# citizen_science_flora_RP2040.net
KiCad netlist of a schematic drawn in EAGLE
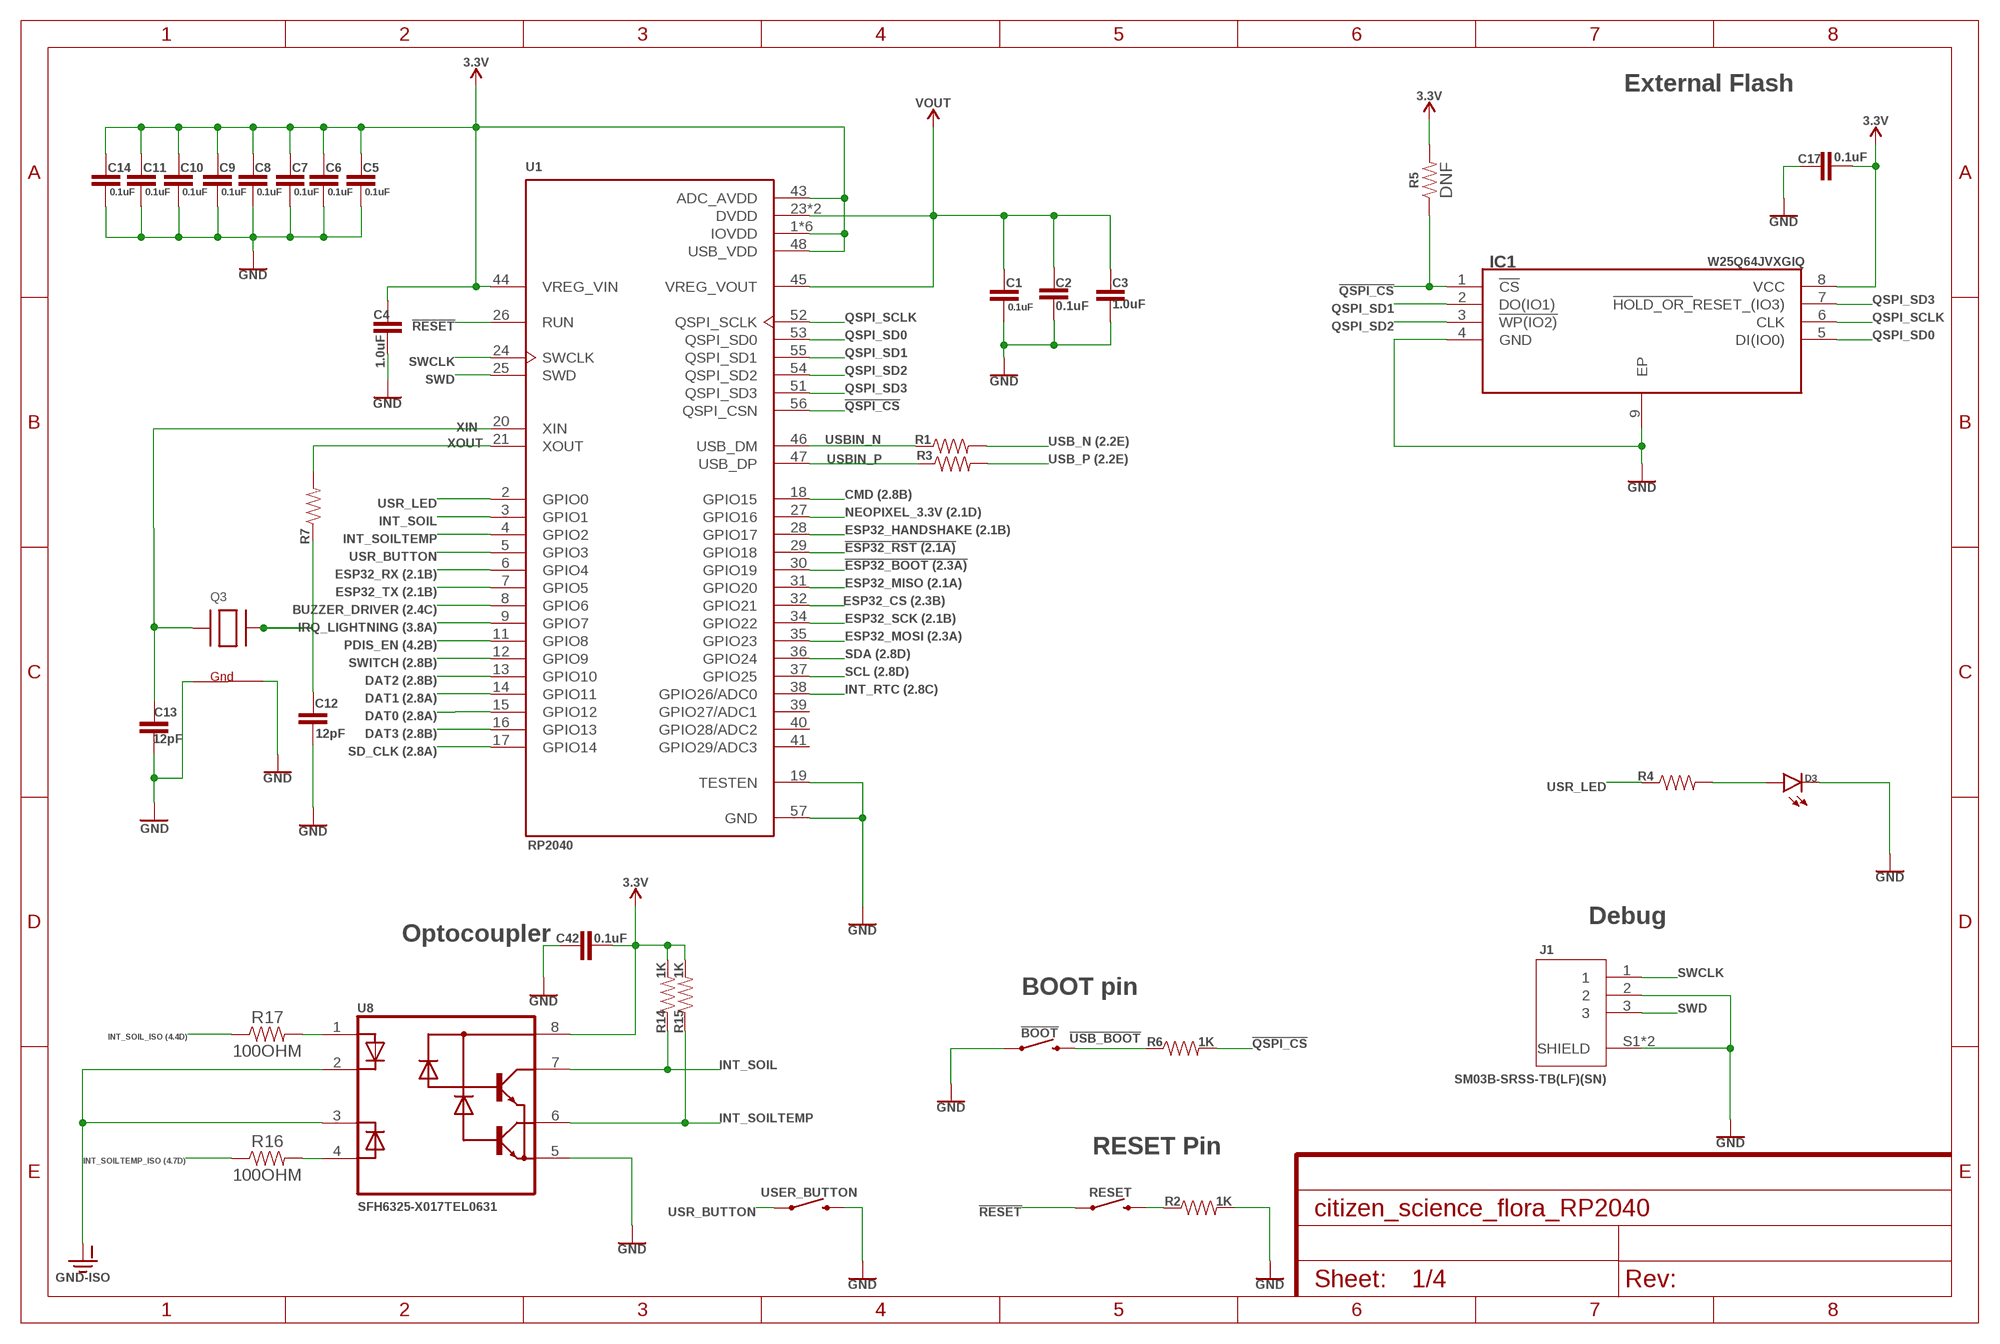
[diagram p0: schematic, sheet 1]
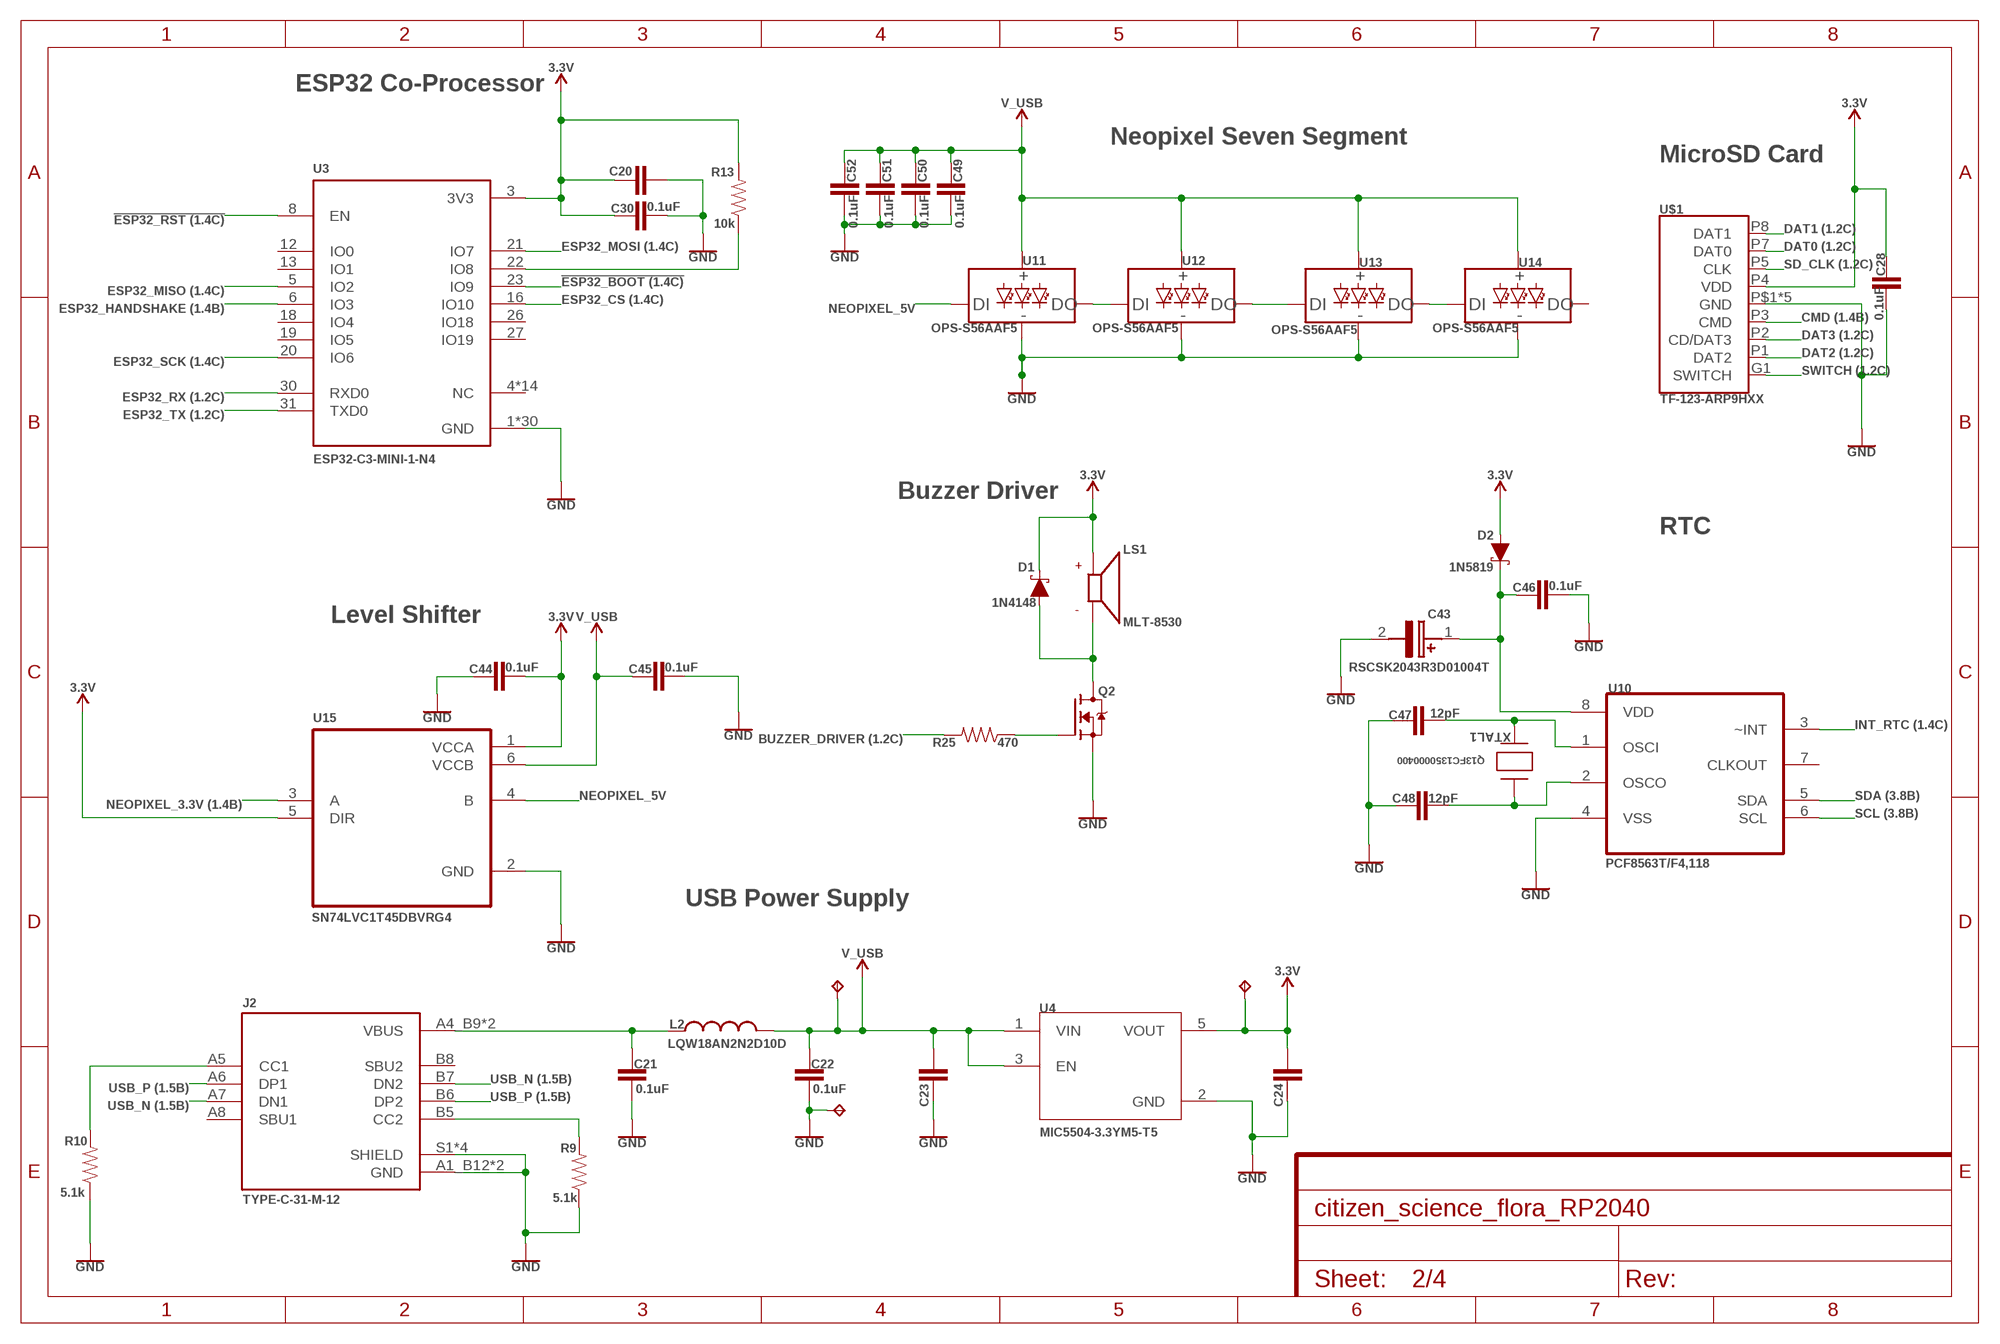
[diagram p1: schematic, sheet 2]
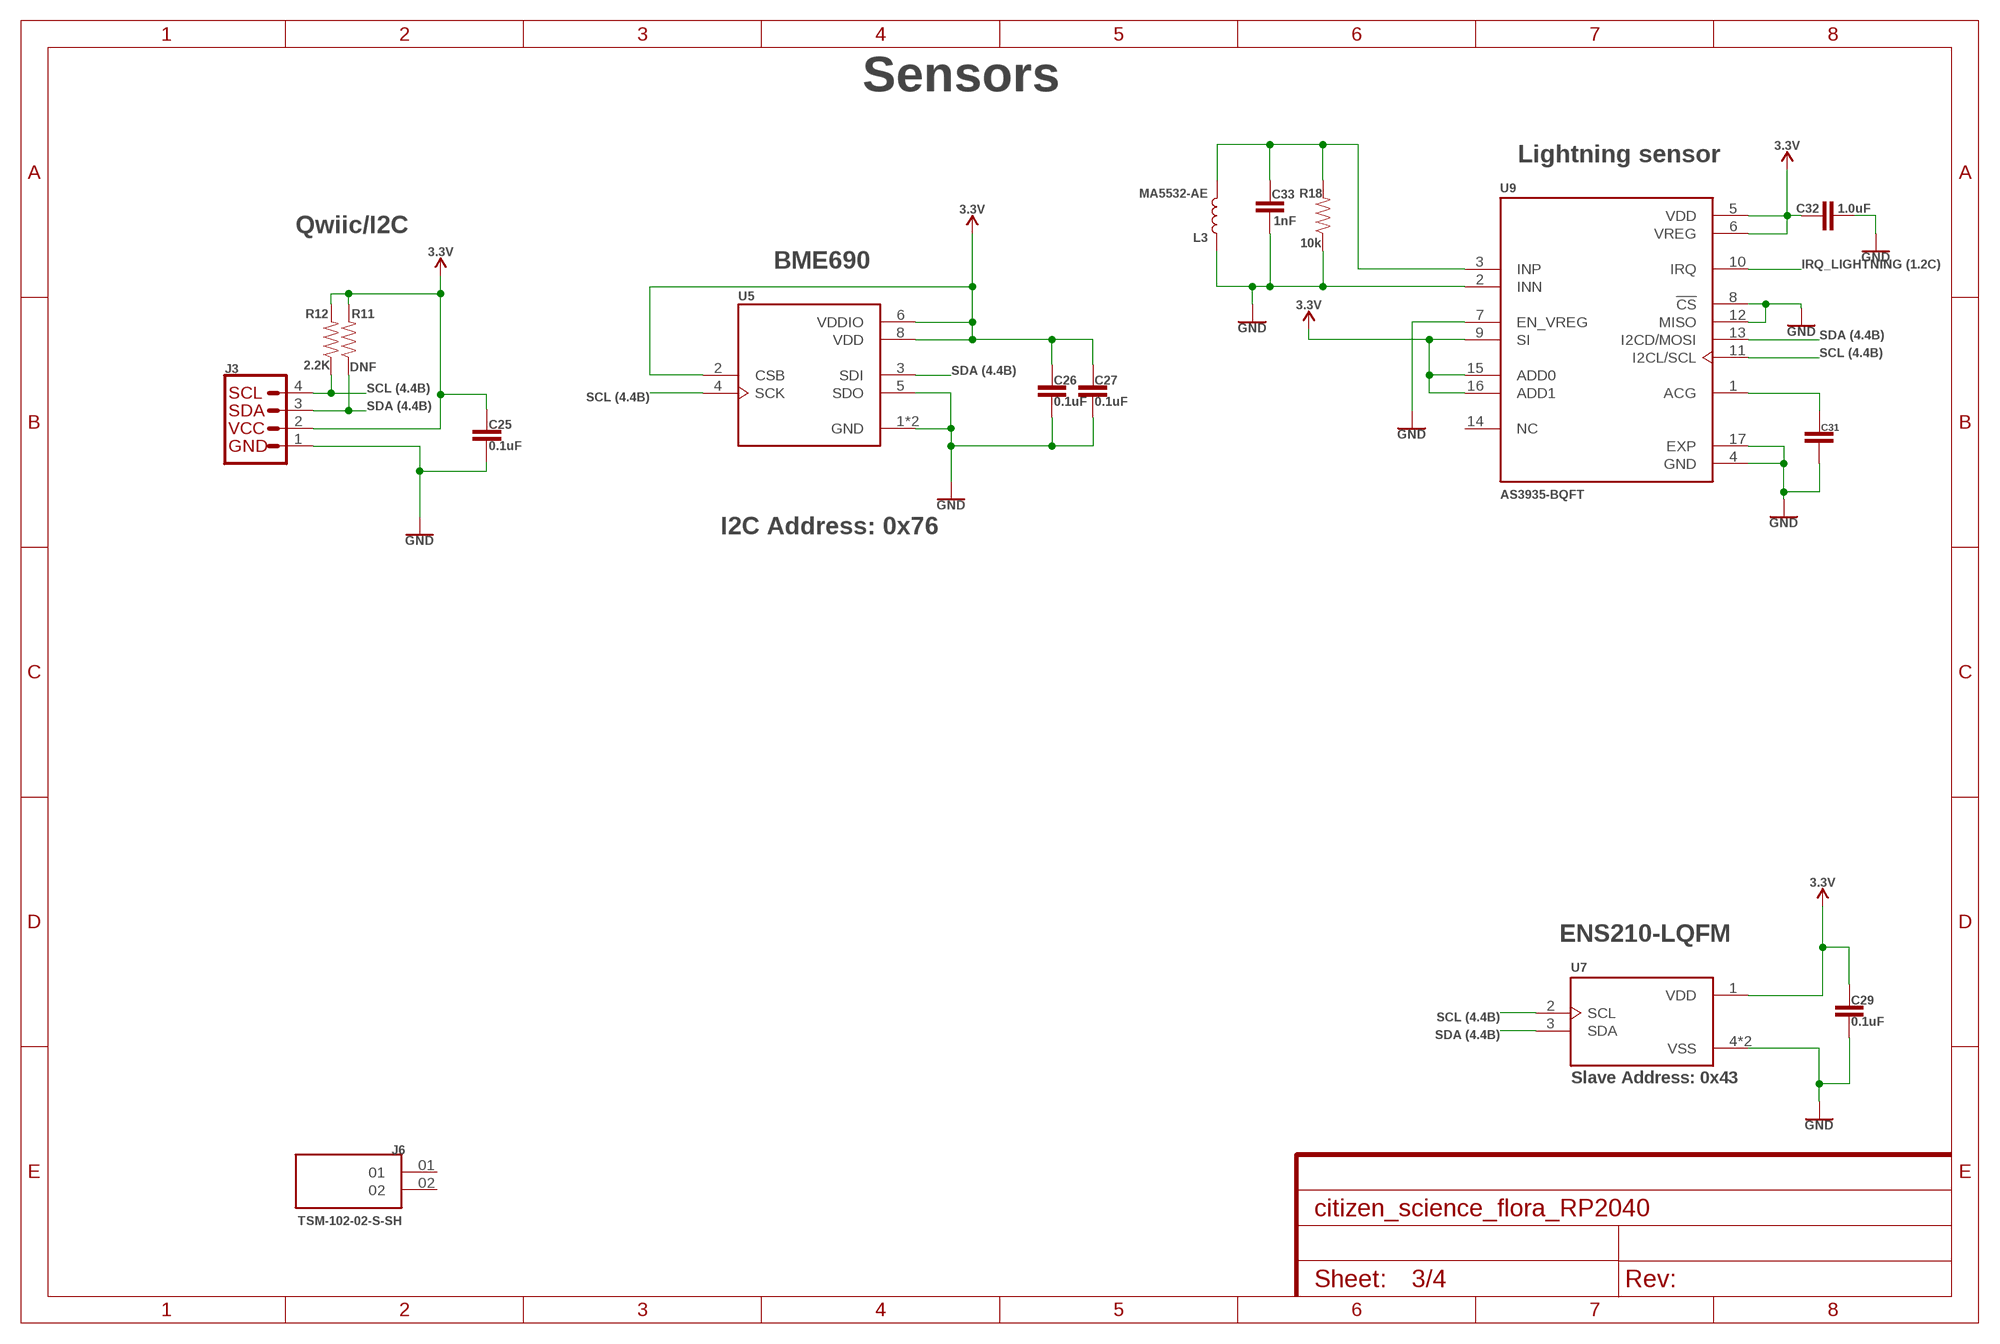
[diagram p2: schematic, sheet 3]
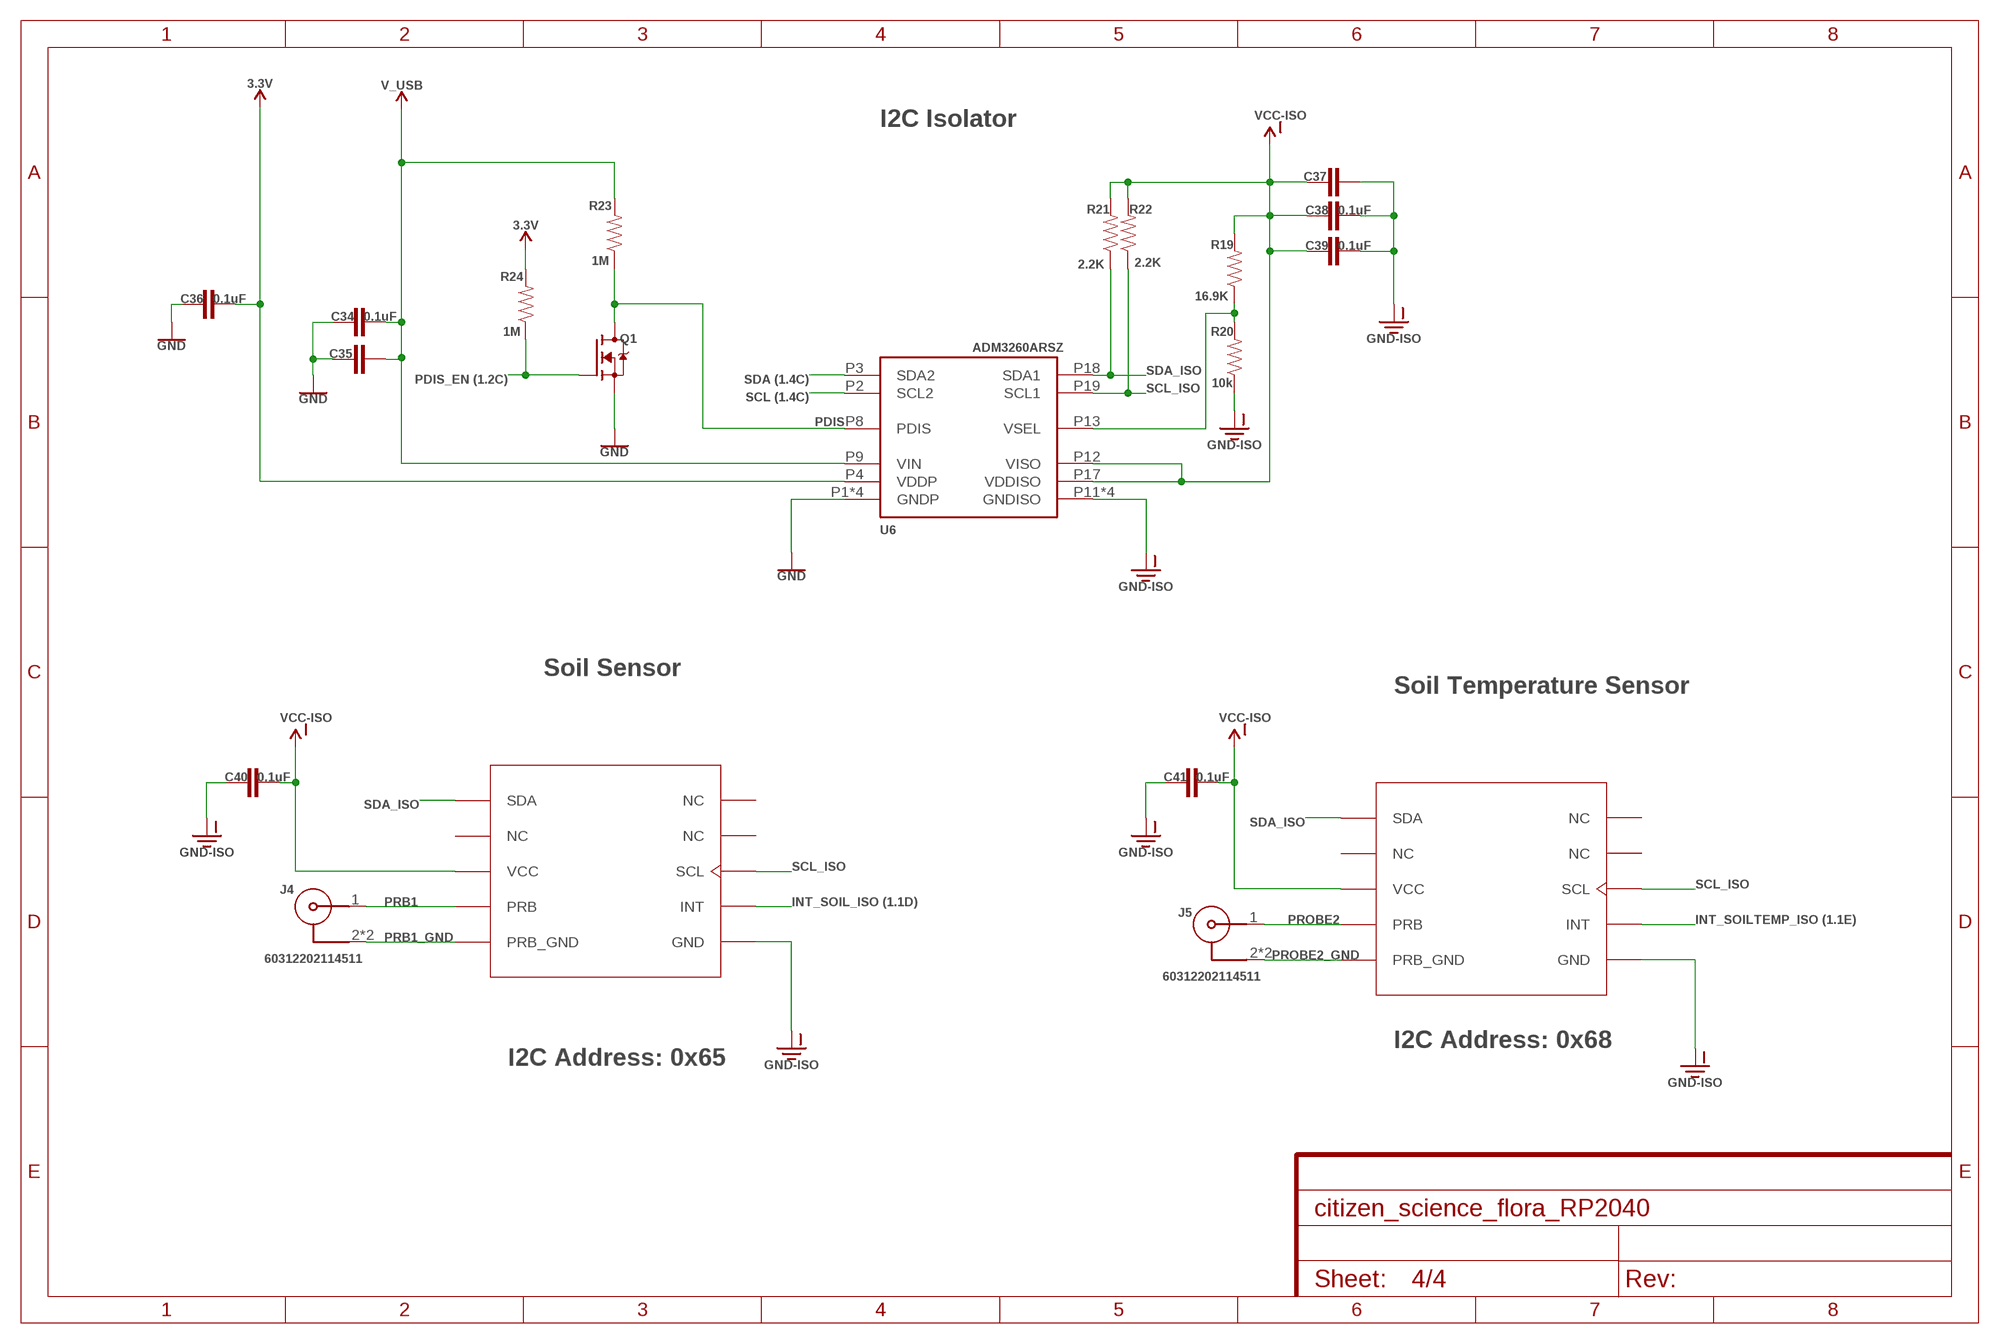
[diagram p3: schematic, sheet 4]

(export (version "E")
  (design (tool "Eeschema 10.0.6"))
  (components
    (comp (ref "C34")
      (value "0.1uF")
      (footprint "eagle-import:0402")
      (libsource (lib "eagle-import") (part "0.1UF-0402-6.3V-10%-X7R"))
    )
    (comp (ref "C35")
      (value "10UF0402")
      (footprint "eagle-import:0402")
      (libsource (lib "eagle-import") (part "10UF0402"))
    )
    (comp (ref "C36")
      (value "0.1uF")
      (footprint "eagle-import:0402")
      (libsource (lib "eagle-import") (part "0.1UF-0402-6.3V-10%-X7R"))
    )
    (comp (ref "C37")
      (value "10UF0402")
      (footprint "eagle-import:0402")
      (libsource (lib "eagle-import") (part "10UF0402"))
    )
    (comp (ref "C38")
      (value "0.1uF")
      (footprint "eagle-import:0402")
      (libsource (lib "eagle-import") (part "0.1UF-0402-6.3V-10%-X7R"))
    )
    (comp (ref "C39")
      (value "0.1uF")
      (footprint "eagle-import:0402")
      (libsource (lib "eagle-import") (part "0.1UF-0402-6.3V-10%-X7R"))
    )
    (comp (ref "C40")
      (value "0.1uF")
      (footprint "eagle-import:0402")
      (libsource (lib "eagle-import") (part "0.1UF-0402-6.3V-10%-X7R"))
    )
    (comp (ref "C41")
      (value "0.1uF")
      (footprint "eagle-import:0402")
      (libsource (lib "eagle-import") (part "0.1UF-0402-6.3V-10%-X7R"))
    )
    (comp (ref "J4")
      (value "60312202114511")
      (footprint "eagle-import:60312202114511")
      (fields (field (name "MF") "Wurth Electronics"))
      (libsource (lib "eagle-import") (part "60312202114511"))
    )
    (comp (ref "J5")
      (value "60312202114511")
      (footprint "eagle-import:60312202114511")
      (fields (field (name "MF") "Wurth Electronics"))
      (libsource (lib "eagle-import") (part "60312202114511"))
    )
    (comp (ref "Q1")
      (value "BSS138")
      (footprint "eagle-import:SOT95P240X111-3N")
      (fields (field (name "MF") "onsemi"))
      (libsource (lib "eagle-import") (part "BSS138"))
    )
    (comp (ref "R19")
      (value "16.9K")
      (footprint "eagle-import:0402")
      (libsource (lib "eagle-import") (part "RESISTOR0402"))
    )
    (comp (ref "R20")
      (value "10k")
      (footprint "eagle-import:0402")
      (libsource (lib "eagle-import") (part "SparkFun-Resistors_Sai_10KOHM-0402-1/16W-1%"))
    )
    (comp (ref "R21")
      (value "2.2K")
      (footprint "eagle-import:0402")
      (libsource (lib "eagle-import") (part "2.2KOHM-0402-1/16W-1%"))
    )
    (comp (ref "R22")
      (value "2.2K")
      (footprint "eagle-import:0402")
      (libsource (lib "eagle-import") (part "2.2KOHM-0402-1/16W-1%"))
    )
    (comp (ref "R23")
      (value "1M")
      (footprint "eagle-import:0402")
      (libsource (lib "eagle-import") (part "1MOHM-0402-1/16W-5%"))
    )
    (comp (ref "R24")
      (value "1M")
      (footprint "eagle-import:0402")
      (libsource (lib "eagle-import") (part "1MOHM-0402-1/16W-5%"))
    )
    (comp (ref "U$2")
      (value "PH-OEM")
      (footprint "eagle-import:PH_SENSOR")
      (libsource (lib "eagle-import") (part "PH-OEM"))
    )
    (comp (ref "U$3")
      (value "PH-OEM")
      (footprint "eagle-import:PH_SENSOR")
      (libsource (lib "eagle-import") (part "PH-OEM"))
    )
    (comp (ref "U6")
      (value "ADM3260ARSZ")
      (footprint "eagle-import:SSOP20")
      (fields (field (name "MF") "Analog Devices"))
      (libsource (lib "eagle-import") (part "ADM3260ARSZ"))
    )
    (comp (ref "!BOOT")
      (value "MOMENTARY-SWITCH-SPST-SMD-4.6X2.8MM")
      (footprint "eagle-import:TACTILE_SWITCH_SMD_4.6X2.8MM")
      (libsource (lib "eagle-import") (part "MOMENTARY-SWITCH-SPST-SMD-4.6X2.8MM"))
    )
    (comp (ref "C1")
      (value "0.1uF")
      (footprint "eagle-import:0402")
      (libsource (lib "eagle-import") (part "SparkFun-Capacitors_Sai_0.1UF-0402-6.3V-10%-X7R"))
    )
    (comp (ref "C2")
      (value "0.1uF")
      (footprint "eagle-import:0402")
      (libsource (lib "eagle-import") (part "SparkFun-Capacitors_Sai_0.1UF-0402-6.3V-10%-X7R"))
    )
    (comp (ref "C3")
      (value "1.0uF")
      (footprint "eagle-import:0402")
      (libsource (lib "eagle-import") (part "SparkFun-Capacitors_Sai_1.0UF-0402-16V-10%"))
    )
    (comp (ref "C4")
      (value "1.0uF")
      (footprint "eagle-import:0402")
      (libsource (lib "eagle-import") (part "SparkFun-Capacitors_Sai_1.0UF-0402-16V-10%"))
    )
    (comp (ref "C5")
      (value "0.1uF")
      (footprint "eagle-import:0402")
      (libsource (lib "eagle-import") (part "SparkFun-Capacitors_Sai_0.1UF-0402-6.3V-10%-X7R"))
    )
    (comp (ref "C6")
      (value "0.1uF")
      (footprint "eagle-import:0402")
      (libsource (lib "eagle-import") (part "SparkFun-Capacitors_Sai_0.1UF-0402-6.3V-10%-X7R"))
    )
    (comp (ref "C7")
      (value "0.1uF")
      (footprint "eagle-import:0402")
      (libsource (lib "eagle-import") (part "SparkFun-Capacitors_Sai_0.1UF-0402-6.3V-10%-X7R"))
    )
    (comp (ref "C8")
      (value "0.1uF")
      (footprint "eagle-import:0402")
      (libsource (lib "eagle-import") (part "SparkFun-Capacitors_Sai_0.1UF-0402-6.3V-10%-X7R"))
    )
    (comp (ref "C9")
      (value "0.1uF")
      (footprint "eagle-import:0402")
      (libsource (lib "eagle-import") (part "SparkFun-Capacitors_Sai_0.1UF-0402-6.3V-10%-X7R"))
    )
    (comp (ref "C10")
      (value "0.1uF")
      (footprint "eagle-import:0402")
      (libsource (lib "eagle-import") (part "SparkFun-Capacitors_Sai_0.1UF-0402-6.3V-10%-X7R"))
    )
    (comp (ref "C11")
      (value "0.1uF")
      (footprint "eagle-import:0402")
      (libsource (lib "eagle-import") (part "SparkFun-Capacitors_Sai_0.1UF-0402-6.3V-10%-X7R"))
    )
    (comp (ref "C12")
      (value "12pF")
      (footprint "eagle-import:0402")
      (libsource (lib "eagle-import") (part "SparkFun-Capacitors_Sai_12PF-0402-50V-5%"))
    )
    (comp (ref "C13")
      (value "12pF")
      (footprint "eagle-import:0402")
      (libsource (lib "eagle-import") (part "SparkFun-Capacitors_Sai_12PF-0402-50V-5%"))
    )
    (comp (ref "C14")
      (value "0.1uF")
      (footprint "eagle-import:0402")
      (libsource (lib "eagle-import") (part "SparkFun-Capacitors_Sai_0.1UF-0402-6.3V-10%-X7R"))
    )
    (comp (ref "C17")
      (value "0.1uF")
      (footprint "eagle-import:0402")
      (libsource (lib "eagle-import") (part "0.1UF-0402-6.3V-10%-X7R"))
    )
    (comp (ref "C42")
      (value "0.1uF")
      (footprint "eagle-import:0402")
      (libsource (lib "eagle-import") (part "0.1UF-0402-6.3V-10%-X7R"))
    )
    (comp (ref "D3")
      (value "LED0603")
      (footprint "eagle-import:LED-0603")
      (libsource (lib "eagle-import") (part "LED0603"))
    )
    (comp (ref "IC1")
      (value "W25Q64JVXGIQ")
      (footprint "eagle-import:SON80P400X400X50-9N")
      (libsource (lib "eagle-import") (part "W25Q64JVXGIQ"))
    )
    (comp (ref "J1")
      (value "SM03B-SRSS-TB(LF)(SN)")
      (footprint "eagle-import:JST_SM03B-SRSS-TB(LF)(SN)")
      (fields (field (name "MF") "JST Sales America Inc."))
      (libsource (lib "eagle-import") (part "SM03B-SRSS-TB(LF)(SN)"))
    )
    (comp (ref "Q3")
      (value "XTAL-4-3225")
      (footprint "eagle-import:NX3225")
      (libsource (lib "eagle-import") (part "XTAL-4-3225"))
    )
    (comp (ref "R1")
      (value "27OHM0402")
      (footprint "eagle-import:0402")
      (libsource (lib "eagle-import") (part "27OHM0402"))
    )
    (comp (ref "R2")
      (value "1K")
      (footprint "eagle-import:0402")
      (libsource (lib "eagle-import") (part "1KOHM-0402-1/16W-1%"))
    )
    (comp (ref "R3")
      (value "27OHM0402")
      (footprint "eagle-import:0402")
      (libsource (lib "eagle-import") (part "27OHM0402"))
    )
    (comp (ref "R4")
      (value "100OHM")
      (footprint "eagle-import:0402")
      (libsource (lib "eagle-import") (part "100OHM"))
    )
    (comp (ref "R5")
      (value "DNF")
      (footprint "eagle-import:0402")
      (libsource (lib "eagle-import") (part "RESISTOR0402"))
    )
    (comp (ref "R6")
      (value "1K")
      (footprint "eagle-import:0402")
      (libsource (lib "eagle-import") (part "1KOHM-0402-1/16W-1%"))
    )
    (comp (ref "R7")
      (value "1KOHM-0402-1/16W-1%")
      (footprint "eagle-import:0402")
      (libsource (lib "eagle-import") (part "SparkFun-Resistors_Sai_1KOHM-0402-1/16W-1%"))
    )
    (comp (ref "R14")
      (value "1K")
      (footprint "eagle-import:0402")
      (libsource (lib "eagle-import") (part "1KOHM-0402-1/16W-1%"))
    )
    (comp (ref "R15")
      (value "1K")
      (footprint "eagle-import:0402")
      (libsource (lib "eagle-import") (part "1KOHM-0402-1/16W-1%"))
    )
    (comp (ref "R16")
      (value "100OHM")
      (footprint "eagle-import:0402")
      (libsource (lib "eagle-import") (part "100OHM"))
    )
    (comp (ref "R17")
      (value "100OHM")
      (footprint "eagle-import:0402")
      (libsource (lib "eagle-import") (part "100OHM"))
    )
    (comp (ref "RESET")
      (value "MOMENTARY-SWITCH-SPST-SMD-4.6X2.8MM")
      (footprint "eagle-import:TACTILE_SWITCH_SMD_4.6X2.8MM")
      (libsource (lib "eagle-import") (part "MOMENTARY-SWITCH-SPST-SMD-4.6X2.8MM"))
    )
    (comp (ref "U1")
      (value "RP2040")
      (footprint "eagle-import:QFN40P700X700X90-57N")
      (fields (field (name "MF") "Raspberry Pi"))
      (libsource (lib "eagle-import") (part "RP2040"))
    )
    (comp (ref "U8")
      (value "SFH6325-X017TEL0631")
      (footprint "eagle-import:SOIC127P599X175-8N")
      (libsource (lib "eagle-import") (part "SFH6325-X017TEL0631"))
    )
    (comp (ref "USER_BUTTON")
      (value "MOMENTARY-SWITCH-SPST-SMD-4.6X2.8MM")
      (footprint "eagle-import:TACTILE_SWITCH_SMD_4.6X2.8MM")
      (libsource (lib "eagle-import") (part "MOMENTARY-SWITCH-SPST-SMD-4.6X2.8MM"))
    )
    (comp (ref "C25")
      (value "0.1uF")
      (footprint "eagle-import:0402")
      (libsource (lib "eagle-import") (part "0.1UF-0402-6.3V-10%-X7R"))
    )
    (comp (ref "C26")
      (value "0.1uF")
      (footprint "eagle-import:0402")
      (libsource (lib "eagle-import") (part "0.1UF-0402-6.3V-10%-X7R"))
    )
    (comp (ref "C27")
      (value "0.1uF")
      (footprint "eagle-import:0402")
      (libsource (lib "eagle-import") (part "0.1UF-0402-6.3V-10%-X7R"))
    )
    (comp (ref "C29")
      (value "0.1uF")
      (footprint "eagle-import:0402")
      (libsource (lib "eagle-import") (part "0.1UF-0402-6.3V-10%-X7R"))
    )
    (comp (ref "C31")
      (value "10UF0402")
      (footprint "eagle-import:0402")
      (libsource (lib "eagle-import") (part "10UF0402"))
    )
    (comp (ref "C32")
      (value "1.0uF")
      (footprint "eagle-import:0402")
      (libsource (lib "eagle-import") (part "1.0UF-0402-16V-10%"))
    )
    (comp (ref "C33")
      (value "1nF")
      (footprint "eagle-import:0402")
      (libsource (lib "eagle-import") (part "1.0NF/1000PF-0402-25V-10%-X7R"))
    )
    (comp (ref "J3")
      (value "QWIIC_CONNECTORJS-1MM")
      (footprint "eagle-import:1X04_1MM_RA")
      (libsource (lib "eagle-import") (part "QWIIC_CONNECTORJS-1MM"))
    )
    (comp (ref "J6")
      (value "TSM-102-02-S-SH")
      (footprint "eagle-import:SAMTEC_TSM-102-02-S-SH")
      (fields (field (name "MF") "Samtec"))
      (libsource (lib "eagle-import") (part "TSM-102-02-S-SH"))
    )
    (comp (ref "L3")
      (value "MA5532-AE")
      (footprint "eagle-import:MA5532-AE")
      (fields (field (name "MF") "Coilcraft"))
      (libsource (lib "eagle-import") (part "MA5532-AE"))
    )
    (comp (ref "R11")
      (value "DNF")
      (footprint "eagle-import:0402")
      (libsource (lib "eagle-import") (part "2.2KOHM-0402-1/16W-1%"))
    )
    (comp (ref "R12")
      (value "2.2K")
      (footprint "eagle-import:0402")
      (libsource (lib "eagle-import") (part "2.2KOHM-0402-1/16W-1%"))
    )
    (comp (ref "R18")
      (value "10k")
      (footprint "eagle-import:0402")
      (libsource (lib "eagle-import") (part "SparkFun-Resistors_Sai_10KOHM-0402-1/16W-1%"))
    )
    (comp (ref "U5")
      (value "BME690")
      (footprint "eagle-import:IC_BME688")
      (fields (field (name "MF") "Bosch Sensortec") (field (name "MP") "BME688"))
      (libsource (lib "eagle-import") (part "BME690"))
    )
    (comp (ref "U7")
      (value "ENS210-LQFM")
      (footprint "eagle-import:XDCR_ENS210-LQFM")
      (fields (field (name "MF") "ScioSense"))
      (libsource (lib "eagle-import") (part "ENS210-LQFM"))
    )
    (comp (ref "U9")
      (value "AS3935-BQFT")
      (footprint "eagle-import:QFN65P400X400X80-17N")
      (fields (field (name "MF") "ScioSense"))
      (libsource (lib "eagle-import") (part "AS3935-BQFT"))
    )
    (comp (ref "3.3V")
      (value "TPB1,27")
      (footprint "eagle-import:B1,27")
      (libsource (lib "eagle-import") (part "TPB1,27"))
    )
    (comp (ref "C20")
      (value "10UF0402")
      (footprint "eagle-import:0402")
      (libsource (lib "eagle-import") (part "10UF0402"))
    )
    (comp (ref "C21")
      (value "0.1uF")
      (footprint "eagle-import:0402")
      (libsource (lib "eagle-import") (part "0.1UF-0402-6.3V-10%-X7R"))
    )
    (comp (ref "C22")
      (value "0.1uF")
      (footprint "eagle-import:0402")
      (libsource (lib "eagle-import") (part "0.1UF-0402-6.3V-10%-X7R"))
    )
    (comp (ref "C23")
      (value "10UF0402")
      (footprint "eagle-import:0402")
      (libsource (lib "eagle-import") (part "10UF0402"))
    )
    (comp (ref "C24")
      (value "10UF0402")
      (footprint "eagle-import:0402")
      (libsource (lib "eagle-import") (part "10UF0402"))
    )
    (comp (ref "C28")
      (value "0.1uF")
      (footprint "eagle-import:0402")
      (libsource (lib "eagle-import") (part "0.1UF-0402-6.3V-10%-X7R"))
    )
    (comp (ref "C30")
      (value "0.1uF")
      (footprint "eagle-import:0402")
      (libsource (lib "eagle-import") (part "0.1UF-0402-6.3V-10%-X7R"))
    )
    (comp (ref "C43")
      (value "RSCSK2043R3D01004T")
      (footprint "eagle-import:RSCSK2043R3D01004T")
      (fields (field (name "MOUSER_PART_NUMBER") "555-DSK3R3H204T614H2"))
      (libsource (lib "eagle-import") (part "RSCSK2043R3D01004T"))
    )
    (comp (ref "C44")
      (value "0.1uF")
      (footprint "eagle-import:0402")
      (libsource (lib "eagle-import") (part "0.1UF-0402-6.3V-10%-X7R"))
    )
    (comp (ref "C45")
      (value "0.1uF")
      (footprint "eagle-import:0402")
      (libsource (lib "eagle-import") (part "0.1UF-0402-6.3V-10%-X7R"))
    )
    (comp (ref "C46")
      (value "0.1uF")
      (footprint "eagle-import:0402")
      (libsource (lib "eagle-import") (part "0.1UF-0402-6.3V-10%-X7R"))
    )
    (comp (ref "C47")
      (value "12pF")
      (footprint "eagle-import:0402")
      (libsource (lib "eagle-import") (part "12PF-0402-50V-5%"))
    )
    (comp (ref "C48")
      (value "12pF")
      (footprint "eagle-import:0402")
      (libsource (lib "eagle-import") (part "12PF-0402-50V-5%"))
    )
    (comp (ref "C49")
      (value "0.1uF")
      (footprint "eagle-import:0402")
      (libsource (lib "eagle-import") (part "0.1UF-0402-6.3V-10%-X7R"))
    )
    (comp (ref "C50")
      (value "0.1uF")
      (footprint "eagle-import:0402")
      (libsource (lib "eagle-import") (part "0.1UF-0402-6.3V-10%-X7R"))
    )
    (comp (ref "C51")
      (value "0.1uF")
      (footprint "eagle-import:0402")
      (libsource (lib "eagle-import") (part "0.1UF-0402-6.3V-10%-X7R"))
    )
    (comp (ref "C52")
      (value "0.1uF")
      (footprint "eagle-import:0402")
      (libsource (lib "eagle-import") (part "0.1UF-0402-6.3V-10%-X7R"))
    )
    (comp (ref "D1")
      (value "1N4148")
      (footprint "eagle-import:SOD-323")
      (libsource (lib "eagle-import") (part "DIODE-SCHOTTKY-BAT60A"))
    )
    (comp (ref "D2")
      (value "1N5819")
      (footprint "eagle-import:SOD-323")
      (libsource (lib "eagle-import") (part "DIODE-SCHOTTKY-BAT20J"))
    )
    (comp (ref "GND")
      (value "TPB1,27")
      (footprint "eagle-import:B1,27")
      (libsource (lib "eagle-import") (part "TPB1,27"))
    )
    (comp (ref "J2")
      (value "TYPE-C-31-M-12")
      (footprint "eagle-import:HRO_TYPE-C-31-M-12")
      (fields (field (name "MF") "HRO Electronics Co., Ltd."))
      (libsource (lib "eagle-import") (part "TYPE-C-31-M-12"))
    )
    (comp (ref "L2")
      (value "LQW18AN2N2D10D")
      (footprint "eagle-import:INDC1608X100N")
      (fields (field (name "MF") "Murata"))
      (libsource (lib "eagle-import") (part "LQW18AN2N2D10D"))
    )
    (comp (ref "LS1")
      (value "MLT-8530")
      (footprint "eagle-import:XDCR_CMT-8504-100-SMT-TR")
      (fields (field (name "MANUFACTURER") "CUI Inc."))
      (libsource (lib "eagle-import") (part "CMT-8504-100-SMT-TR"))
    )
    (comp (ref "Q2")
      (value "BSS138")
      (footprint "eagle-import:SOT95P240X111-3N")
      (fields (field (name "MF") "onsemi"))
      (libsource (lib "eagle-import") (part "BSS138"))
    )
    (comp (ref "R9")
      (value "5.1k")
      (footprint "eagle-import:0402")
      (libsource (lib "eagle-import") (part "5.1KOHM-0402-1/16W-1%"))
    )
    (comp (ref "R10")
      (value "5.1k")
      (footprint "eagle-import:0402")
      (libsource (lib "eagle-import") (part "5.1KOHM-0402-1/16W-1%"))
    )
    (comp (ref "R13")
      (value "10k")
      (footprint "eagle-import:0402")
      (libsource (lib "eagle-import") (part "10KOHM-0402-1/16W-1%"))
    )
    (comp (ref "R25")
      (value "470")
      (footprint "eagle-import:0402")
      (libsource (lib "eagle-import") (part "10KOHM-0402-1/16W-1%"))
    )
    (comp (ref "U$1")
      (value "TF-123-ARP9HXX")
      (footprint "eagle-import:MICROSDCARD")
      (libsource (lib "eagle-import") (part "TF-123-ARP9HXX"))
    )
    (comp (ref "U3")
      (value "ESP32-C3-MINI-1-N4")
      (footprint "eagle-import:XCVR_ESP32-C3-MINI-1-N4")
      (fields (field (name "MF") "Espressif Systems"))
      (libsource (lib "eagle-import") (part "ESP32-C3-MINI-1-N4"))
    )
    (comp (ref "U4")
      (value "MIC5504-3.3YM5-T5")
      (footprint "eagle-import:SOT95P280X145-5N")
      (fields (field (name "MF") "Microchip"))
      (libsource (lib "eagle-import") (part "MIC5504-3.3YM5-T5"))
    )
    (comp (ref "U10")
      (value "PCF8563T/F4,118")
      (footprint "eagle-import:SOIC127P600X175-8N")
      (fields (field (name "MF") "NXP USA"))
      (libsource (lib "eagle-import") (part "PCF8563T/F4,118"))
    )
    (comp (ref "U11")
      (value "OPS-S56AAF5")
      (footprint "eagle-import:OPS-S56AAF5")
      (libsource (lib "eagle-import") (part "OPS-S56AAF5"))
    )
    (comp (ref "U12")
      (value "OPS-S56AAF5")
      (footprint "eagle-import:OPS-S56AAF5")
      (libsource (lib "eagle-import") (part "OPS-S56AAF5"))
    )
    (comp (ref "U13")
      (value "OPS-S56AAF5")
      (footprint "eagle-import:OPS-S56AAF5")
      (libsource (lib "eagle-import") (part "OPS-S56AAF5"))
    )
    (comp (ref "U14")
      (value "OPS-S56AAF5")
      (footprint "eagle-import:OPS-S56AAF5")
      (libsource (lib "eagle-import") (part "OPS-S56AAF5"))
    )
    (comp (ref "U15")
      (value "SN74LVC1T45DBVRG4")
      (footprint "eagle-import:SOT95P280X145-6N")
      (fields (field (name "MF") "Texas Instruments"))
      (libsource (lib "eagle-import") (part "SN74LVC1T45DBVRG4"))
    )
    (comp (ref "USB")
      (value "V_USB")
      (footprint "eagle-import:B1,27")
      (libsource (lib "eagle-import") (part "TPB1,27"))
    )
    (comp (ref "XTAL1")
      (value "Q13FC1350000400")
      (footprint "eagle-import:XTAL_FC-135_EPS")
      (fields (field (name "MF") "EPSON"))
      (libsource (lib "eagle-import") (part "Q13FC1350000400"))
    )
  )
  (nets
    (net (code "1") (name "3.3V") (class "Default")
      (node (ref "3.3V") (pin "TP") (pinfunction "TP_TP") (pintype "input"))
      (node (ref "C10") (pin "1") (pinfunction "1_1") (pintype "passive"))
      (node (ref "C11") (pin "1") (pinfunction "1_1") (pintype "passive"))
      (node (ref "C14") (pin "1") (pinfunction "1_1") (pintype "passive"))
      (node (ref "C17") (pin "2") (pinfunction "2_2") (pintype "passive"))
      (node (ref "C20") (pin "1") (pinfunction "1_1") (pintype "passive"))
      (node (ref "C24") (pin "2") (pinfunction "2_2") (pintype "passive"))
      (node (ref "C25") (pin "1") (pinfunction "1_1") (pintype "passive"))
      (node (ref "C26") (pin "1") (pinfunction "1_1") (pintype "passive"))
      (node (ref "C27") (pin "1") (pinfunction "1_1") (pintype "passive"))
      (node (ref "C28") (pin "1") (pinfunction "1_1") (pintype "passive"))
      (node (ref "C29") (pin "1") (pinfunction "1_1") (pintype "passive"))
      (node (ref "C30") (pin "1") (pinfunction "1_1") (pintype "passive"))
      (node (ref "C32") (pin "1") (pinfunction "1_1") (pintype "passive"))
      (node (ref "C36") (pin "2") (pinfunction "2_2") (pintype "passive"))
      (node (ref "C4") (pin "1") (pinfunction "1_1") (pintype "passive"))
      (node (ref "C42") (pin "2") (pinfunction "2_2") (pintype "passive"))
      (node (ref "C44") (pin "2") (pinfunction "2_2") (pintype "passive"))
      (node (ref "C5") (pin "1") (pinfunction "1_1") (pintype "passive"))
      (node (ref "C6") (pin "1") (pinfunction "1_1") (pintype "passive"))
      (node (ref "C7") (pin "1") (pinfunction "1_1") (pintype "passive"))
      (node (ref "C8") (pin "1") (pinfunction "1_1") (pintype "passive"))
      (node (ref "C9") (pin "1") (pinfunction "1_1") (pintype "passive"))
      (node (ref "D1") (pin "C") (pinfunction "C_C") (pintype "passive"))
      (node (ref "D2") (pin "A") (pinfunction "A_A") (pintype "passive"))
      (node (ref "IC1") (pin "8") (pinfunction "VCC_8") (pintype "bidirectional"))
      (node (ref "J3") (pin "2") (pinfunction "2_2") (pintype "power_in"))
      (node (ref "LS1") (pin "P") (pinfunction "P_P") (pintype "passive"))
      (node (ref "R11") (pin "2") (pinfunction "2_2") (pintype "passive"))
      (node (ref "R12") (pin "2") (pinfunction "2_2") (pintype "passive"))
      (node (ref "R13") (pin "2") (pinfunction "2_2") (pintype "passive"))
      (node (ref "R14") (pin "2") (pinfunction "2_2") (pintype "passive"))
      (node (ref "R15") (pin "2") (pinfunction "2_2") (pintype "passive"))
      (node (ref "R24") (pin "2") (pinfunction "2_2") (pintype "passive"))
      (node (ref "R5") (pin "2") (pinfunction "2_2") (pintype "passive"))
      (node (ref "U$1") (pin "P4") (pinfunction "VDD_P4") (pintype "power_in"))
      (node (ref "U1") (pin "1") (pinfunction "IOVDD_1") (pintype "power_in"))
      (node (ref "U1") (pin "10") (pinfunction "IOVDD_10") (pintype "power_in"))
      (node (ref "U1") (pin "22") (pinfunction "IOVDD_22") (pintype "power_in"))
      (node (ref "U1") (pin "33") (pinfunction "IOVDD_33") (pintype "power_in"))
      (node (ref "U1") (pin "42") (pinfunction "IOVDD_42") (pintype "power_in"))
      (node (ref "U1") (pin "43") (pinfunction "ADC_AVDD_43") (pintype "power_in"))
      (node (ref "U1") (pin "44") (pinfunction "VREG_VIN_44") (pintype "input"))
      (node (ref "U1") (pin "48") (pinfunction "USB_VDD_48") (pintype "power_in"))
      (node (ref "U1") (pin "49") (pinfunction "IOVDD_49") (pintype "power_in"))
      (node (ref "U15") (pin "1") (pinfunction "VCCA_1") (pintype "power_in"))
      (node (ref "U15") (pin "5") (pinfunction "DIR_5") (pintype "input"))
      (node (ref "U3") (pin "3") (pinfunction "3V3_3") (pintype "power_in"))
      (node (ref "U4") (pin "5") (pinfunction "VOUT_5") (pintype "output"))
      (node (ref "U5") (pin "2") (pinfunction "CSB_2") (pintype "input"))
      (node (ref "U5") (pin "6") (pinfunction "VDDIO_6") (pintype "power_in"))
      (node (ref "U5") (pin "8") (pinfunction "VDD_8") (pintype "power_in"))
      (node (ref "U6") (pin "P4") (pinfunction "VDDP_P4") (pintype "bidirectional"))
      (node (ref "U7") (pin "1") (pinfunction "VDD_1") (pintype "power_in"))
      (node (ref "U8") (pin "8") (pinfunction "C(VCC)_8") (pintype "passive"))
      (node (ref "U9") (pin "15") (pinfunction "ADD0_15") (pintype "input"))
      (node (ref "U9") (pin "16") (pinfunction "ADD1_16") (pintype "input"))
      (node (ref "U9") (pin "5") (pinfunction "VDD_5") (pintype "power_in"))
      (node (ref "U9") (pin "6") (pinfunction "VREG_6") (pintype "power_in"))
      (node (ref "U9") (pin "9") (pinfunction "SI_9") (pintype "input"))
    )
    (net (code "2") (name "BUZZER_DRIVER") (class "Default")
      (node (ref "R25") (pin "2") (pinfunction "2_2") (pintype "passive"))
      (node (ref "U1") (pin "8") (pinfunction "GPIO6_8") (pintype "bidirectional"))
    )
    (net (code "3") (name "CMD") (class "Default")
      (node (ref "U$1") (pin "P3") (pinfunction "CMD_P3") (pintype "bidirectional"))
      (node (ref "U1") (pin "18") (pinfunction "GPIO15_18") (pintype "bidirectional"))
    )
    (net (code "4") (name "DAT0") (class "Default")
      (node (ref "U$1") (pin "P7") (pinfunction "DAT0_P7") (pintype "bidirectional"))
      (node (ref "U1") (pin "15") (pinfunction "GPIO12_15") (pintype "bidirectional"))
    )
    (net (code "5") (name "DAT1") (class "Default")
      (node (ref "U$1") (pin "P8") (pinfunction "DAT1_P8") (pintype "bidirectional"))
      (node (ref "U1") (pin "14") (pinfunction "GPIO11_14") (pintype "bidirectional"))
    )
    (net (code "6") (name "DAT2") (class "Default")
      (node (ref "U$1") (pin "P1") (pinfunction "DAT2_P1") (pintype "bidirectional"))
      (node (ref "U1") (pin "13") (pinfunction "GPIO10_13") (pintype "bidirectional"))
    )
    (net (code "7") (name "DAT3") (class "Default")
      (node (ref "U$1") (pin "P2") (pinfunction "CD/DAT3_P2") (pintype "bidirectional"))
      (node (ref "U1") (pin "16") (pinfunction "GPIO13_16") (pintype "bidirectional"))
    )
    (net (code "8") (name "ESP32_CS") (class "Default")
      (node (ref "U1") (pin "32") (pinfunction "GPIO21_32") (pintype "bidirectional"))
      (node (ref "U3") (pin "16") (pinfunction "IO10_16") (pintype "bidirectional"))
    )
    (net (code "9") (name "ESP32_HANDSHAKE") (class "Default")
      (node (ref "U1") (pin "28") (pinfunction "GPIO17_28") (pintype "bidirectional"))
      (node (ref "U3") (pin "6") (pinfunction "IO3_6") (pintype "bidirectional"))
    )
    (net (code "10") (name "ESP32_MISO") (class "Default")
      (node (ref "U1") (pin "31") (pinfunction "GPIO20_31") (pintype "bidirectional"))
      (node (ref "U3") (pin "5") (pinfunction "IO2_5") (pintype "bidirectional"))
    )
    (net (code "11") (name "ESP32_MOSI") (class "Default")
      (node (ref "U1") (pin "35") (pinfunction "GPIO23_35") (pintype "bidirectional"))
      (node (ref "U3") (pin "21") (pinfunction "IO7_21") (pintype "bidirectional"))
    )
    (net (code "12") (name "ESP32_RX") (class "Default")
      (node (ref "U1") (pin "6") (pinfunction "GPIO4_6") (pintype "bidirectional"))
      (node (ref "U3") (pin "30") (pinfunction "RXD0_30") (pintype "bidirectional"))
    )
    (net (code "13") (name "ESP32_SCK") (class "Default")
      (node (ref "U1") (pin "34") (pinfunction "GPIO22_34") (pintype "bidirectional"))
      (node (ref "U3") (pin "20") (pinfunction "IO6_20") (pintype "bidirectional"))
    )
    (net (code "14") (name "ESP32_TX") (class "Default")
      (node (ref "U1") (pin "7") (pinfunction "GPIO5_7") (pintype "bidirectional"))
      (node (ref "U3") (pin "31") (pinfunction "TXD0_31") (pintype "bidirectional"))
    )
    (net (code "15") (name "GND") (class "Default")
      (node (ref "!BOOT") (pin "1") (pinfunction "1_1") (pintype "passive"))
      (node (ref "!BOOT") (pin "2") (pinfunction "1_2") (pintype "passive"))
      (node (ref "C1") (pin "2") (pinfunction "2_2") (pintype "passive"))
      (node (ref "C10") (pin "2") (pinfunction "2_2") (pintype "passive"))
      (node (ref "C11") (pin "2") (pinfunction "2_2") (pintype "passive"))
      (node (ref "C12") (pin "1") (pinfunction "1_1") (pintype "passive"))
      (node (ref "C13") (pin "1") (pinfunction "1_1") (pintype "passive"))
      (node (ref "C14") (pin "2") (pinfunction "2_2") (pintype "passive"))
      (node (ref "C17") (pin "1") (pinfunction "1_1") (pintype "passive"))
      (node (ref "C2") (pin "2") (pinfunction "2_2") (pintype "passive"))
      (node (ref "C20") (pin "2") (pinfunction "2_2") (pintype "passive"))
      (node (ref "C21") (pin "2") (pinfunction "2_2") (pintype "passive"))
      (node (ref "C22") (pin "2") (pinfunction "2_2") (pintype "passive"))
      (node (ref "C23") (pin "1") (pinfunction "1_1") (pintype "passive"))
      (node (ref "C24") (pin "1") (pinfunction "1_1") (pintype "passive"))
      (node (ref "C25") (pin "2") (pinfunction "2_2") (pintype "passive"))
      (node (ref "C26") (pin "2") (pinfunction "2_2") (pintype "passive"))
      (node (ref "C27") (pin "2") (pinfunction "2_2") (pintype "passive"))
      (node (ref "C28") (pin "2") (pinfunction "2_2") (pintype "passive"))
      (node (ref "C29") (pin "2") (pinfunction "2_2") (pintype "passive"))
      (node (ref "C3") (pin "2") (pinfunction "2_2") (pintype "passive"))
      (node (ref "C30") (pin "2") (pinfunction "2_2") (pintype "passive"))
      (node (ref "C31") (pin "2") (pinfunction "2_2") (pintype "passive"))
      (node (ref "C32") (pin "2") (pinfunction "2_2") (pintype "passive"))
      (node (ref "C33") (pin "2") (pinfunction "2_2") (pintype "passive"))
      (node (ref "C34") (pin "1") (pinfunction "1_1") (pintype "passive"))
      (node (ref "C35") (pin "1") (pinfunction "1_1") (pintype "passive"))
      (node (ref "C36") (pin "1") (pinfunction "1_1") (pintype "passive"))
      (node (ref "C4") (pin "2") (pinfunction "2_2") (pintype "passive"))
      (node (ref "C42") (pin "1") (pinfunction "1_1") (pintype "passive"))
      (node (ref "C43") (pin "2") (pinfunction "-_2") (pintype "bidirectional"))
      (node (ref "C44") (pin "1") (pinfunction "1_1") (pintype "passive"))
      (node (ref "C45") (pin "2") (pinfunction "2_2") (pintype "passive"))
      (node (ref "C46") (pin "2") (pinfunction "2_2") (pintype "passive"))
      (node (ref "C47") (pin "1") (pinfunction "1_1") (pintype "passive"))
      (node (ref "C48") (pin "1") (pinfunction "1_1") (pintype "passive"))
      (node (ref "C49") (pin "2") (pinfunction "2_2") (pintype "passive"))
      (node (ref "C5") (pin "2") (pinfunction "2_2") (pintype "passive"))
      (node (ref "C50") (pin "2") (pinfunction "2_2") (pintype "passive"))
      (node (ref "C51") (pin "2") (pinfunction "2_2") (pintype "passive"))
      (node (ref "C52") (pin "2") (pinfunction "2_2") (pintype "passive"))
      (node (ref "C6") (pin "2") (pinfunction "2_2") (pintype "passive"))
      (node (ref "C7") (pin "2") (pinfunction "2_2") (pintype "passive"))
      (node (ref "C8") (pin "2") (pinfunction "2_2") (pintype "passive"))
      (node (ref "C9") (pin "2") (pinfunction "2_2") (pintype "passive"))
      (node (ref "D3") (pin "C") (pinfunction "C_C") (pintype "passive"))
      (node (ref "GND") (pin "TP") (pinfunction "TP_TP") (pintype "input"))
      (node (ref "IC1") (pin "4") (pinfunction "GND_4") (pintype "bidirectional"))
      (node (ref "IC1") (pin "9") (pinfunction "EP_9") (pintype "bidirectional"))
      (node (ref "J1") (pin "2") (pinfunction "2_2") (pintype "passive"))
      (node (ref "J1") (pin "S1") (pinfunction "SHIELD_S1") (pintype "passive"))
      (node (ref "J1") (pin "S2") (pinfunction "SHIELD_S2") (pintype "passive"))
      (node (ref "J2") (pin "A1_B12") (pinfunction "GND_A1_B12") (pintype "power_in"))
      (node (ref "J2") (pin "B1_A12") (pinfunction "GND_B1_A12") (pintype "power_in"))
      (node (ref "J2") (pin "S1") (pinfunction "SHIELD_S1") (pintype "passive"))
      (node (ref "J2") (pin "S2") (pinfunction "SHIELD_S2") (pintype "passive"))
      (node (ref "J2") (pin "S3") (pinfunction "SHIELD_S3") (pintype "passive"))
      (node (ref "J2") (pin "S4") (pinfunction "SHIELD_S4") (pintype "passive"))
      (node (ref "J3") (pin "1") (pinfunction "1_1") (pintype "power_in"))
      (node (ref "L3") (pin "1") (pinfunction "1_1") (pintype "passive"))
      (node (ref "Q1") (pin "2") (pinfunction "S_2") (pintype "passive"))
      (node (ref "Q2") (pin "2") (pinfunction "S_2") (pintype "passive"))
      (node (ref "Q3") (pin "2") (pinfunction "G2_2") (pintype "power_in"))
      (node (ref "Q3") (pin "4") (pinfunction "G1_4") (pintype "power_in"))
      (node (ref "R10") (pin "1") (pinfunction "1_1") (pintype "passive"))
      (node (ref "R18") (pin "1") (pinfunction "1_1") (pintype "passive"))
      (node (ref "R2") (pin "2") (pinfunction "2_2") (pintype "passive"))
      (node (ref "R9") (pin "1") (pinfunction "1_1") (pintype "passive"))
      (node (ref "U$1") (pin "P$1") (pinfunction "GND_P$1") (pintype "power_in"))
      (node (ref "U$1") (pin "P$2") (pinfunction "GND_P$2") (pintype "power_in"))
      (node (ref "U$1") (pin "P$3") (pinfunction "GND_P$3") (pintype "power_in"))
      (node (ref "U$1") (pin "P$4") (pinfunction "GND_P$4") (pintype "power_in"))
      (node (ref "U$1") (pin "P6") (pinfunction "GND_P6") (pintype "power_in"))
      (node (ref "U1") (pin "19") (pinfunction "TESTEN_19") (pintype "passive"))
      (node (ref "U1") (pin "57") (pinfunction "GND_57") (pintype "power_in"))
      (node (ref "U10") (pin "4") (pinfunction "VSS_4") (pintype "power_in"))
      (node (ref "U11") (pin "P$3") (pinfunction "GND_P$3") (pintype "bidirectional"))
      (node (ref "U12") (pin "P$3") (pinfunction "GND_P$3") (pintype "bidirectional"))
      (node (ref "U13") (pin "P$3") (pinfunction "GND_P$3") (pintype "bidirectional"))
      (node (ref "U14") (pin "P$3") (pinfunction "GND_P$3") (pintype "bidirectional"))
      (node (ref "U15") (pin "2") (pinfunction "GND_2") (pintype "power_in"))
      (node (ref "U3") (pin "1") (pinfunction "GND_1") (pintype "power_in"))
      (node (ref "U3") (pin "11") (pinfunction "GND_11") (pintype "power_in"))
      (node (ref "U3") (pin "14") (pinfunction "GND_14") (pintype "power_in"))
      (node (ref "U3") (pin "2") (pinfunction "GND_2") (pintype "power_in"))
      (node (ref "U3") (pin "36") (pinfunction "GND_36") (pintype "power_in"))
      (node (ref "U3") (pin "37") (pinfunction "GND_37") (pintype "power_in"))
      (node (ref "U3") (pin "38") (pinfunction "GND_38") (pintype "power_in"))
      (node (ref "U3") (pin "39") (pinfunction "GND_39") (pintype "power_in"))
      (node (ref "U3") (pin "40") (pinfunction "GND_40") (pintype "power_in"))
      (node (ref "U3") (pin "41") (pinfunction "GND_41") (pintype "power_in"))
      (node (ref "U3") (pin "42") (pinfunction "GND_42") (pintype "power_in"))
      (node (ref "U3") (pin "43") (pinfunction "GND_43") (pintype "power_in"))
      (node (ref "U3") (pin "44") (pinfunction "GND_44") (pintype "power_in"))
      (node (ref "U3") (pin "45") (pinfunction "GND_45") (pintype "power_in"))
      (node (ref "U3") (pin "46") (pinfunction "GND_46") (pintype "power_in"))
      (node (ref "U3") (pin "47") (pinfunction "GND_47") (pintype "power_in"))
      (node (ref "U3") (pin "48") (pinfunction "GND_48") (pintype "power_in"))
      (node (ref "U3") (pin "49_1") (pinfunction "GND_49_1") (pintype "power_in"))
      (node (ref "U3") (pin "49_2") (pinfunction "GND_49_2") (pintype "power_in"))
      (node (ref "U3") (pin "49_3") (pinfunction "GND_49_3") (pintype "power_in"))
      (node (ref "U3") (pin "49_4") (pinfunction "GND_49_4") (pintype "power_in"))
      (node (ref "U3") (pin "49_5") (pinfunction "GND_49_5") (pintype "power_in"))
      (node (ref "U3") (pin "49_6") (pinfunction "GND_49_6") (pintype "power_in"))
      (node (ref "U3") (pin "49_7") (pinfunction "GND_49_7") (pintype "power_in"))
      (node (ref "U3") (pin "49_8") (pinfunction "GND_49_8") (pintype "power_in"))
      (node (ref "U3") (pin "49_9") (pinfunction "GND_49_9") (pintype "power_in"))
      (node (ref "U3") (pin "50") (pinfunction "GND_50") (pintype "power_in"))
      (node (ref "U3") (pin "51") (pinfunction "GND_51") (pintype "power_in"))
      (node (ref "U3") (pin "52") (pinfunction "GND_52") (pintype "power_in"))
      (node (ref "U3") (pin "53") (pinfunction "GND_53") (pintype "power_in"))
      (node (ref "U4") (pin "2") (pinfunction "GND_2") (pintype "power_in"))
      (node (ref "U5") (pin "1") (pinfunction "GND_1") (pintype "power_in"))
      (node (ref "U5") (pin "5") (pinfunction "SDO_5") (pintype "bidirectional"))
      (node (ref "U5") (pin "7") (pinfunction "GND_7") (pintype "power_in"))
      (node (ref "U6") (pin "P1") (pinfunction "GNDP_P1") (pintype "bidirectional"))
      (node (ref "U6") (pin "P10") (pinfunction "GNDP_P10") (pintype "bidirectional"))
      (node (ref "U6") (pin "P5") (pinfunction "GNDP_P5") (pintype "bidirectional"))
      (node (ref "U6") (pin "P7") (pinfunction "GNDP_P7") (pintype "bidirectional"))
      (node (ref "U7") (pin "4") (pinfunction "VSS_4") (pintype "power_in"))
      (node (ref "U7") (pin "5") (pinfunction "VSS_5") (pintype "power_in"))
      (node (ref "U8") (pin "5") (pinfunction "E(GND)_5") (pintype "passive"))
      (node (ref "U9") (pin "12") (pinfunction "MISO_12") (pintype "output"))
      (node (ref "U9") (pin "17") (pinfunction "EXP_17") (pintype "power_in"))
      (node (ref "U9") (pin "2") (pinfunction "INN_2") (pintype "bidirectional"))
      (node (ref "U9") (pin "4") (pinfunction "GND_4") (pintype "power_in"))
      (node (ref "U9") (pin "7") (pinfunction "EN_VREG_7") (pintype "input"))
      (node (ref "U9") (pin "8") (pinfunction "~{CS}_8") (pintype "input"))
      (node (ref "USER_BUTTON") (pin "3") (pinfunction "2_3") (pintype "passive"))
      (node (ref "USER_BUTTON") (pin "4") (pinfunction "2_4") (pintype "passive"))
    )
    (net (code "16") (name "GND-ISO") (class "Default")
      (node (ref "C37") (pin "2") (pinfunction "2_2") (pintype "passive"))
      (node (ref "C38") (pin "2") (pinfunction "2_2") (pintype "passive"))
      (node (ref "C39") (pin "2") (pinfunction "2_2") (pintype "passive"))
      (node (ref "C40") (pin "1") (pinfunction "1_1") (pintype "passive"))
      (node (ref "C41") (pin "1") (pinfunction "1_1") (pintype "passive"))
      (node (ref "R20") (pin "1") (pinfunction "1_1") (pintype "passive"))
      (node (ref "U$2") (pin "P$6") (pinfunction "GND_P$6") (pintype "power_in"))
      (node (ref "U$3") (pin "P$6") (pinfunction "GND_P$6") (pintype "power_in"))
      (node (ref "U6") (pin "P11") (pinfunction "GNDISO_P11") (pintype "bidirectional"))
      (node (ref "U6") (pin "P14") (pinfunction "GNDISO_P14") (pintype "bidirectional"))
      (node (ref "U6") (pin "P16") (pinfunction "GNDISO_P16") (pintype "bidirectional"))
      (node (ref "U6") (pin "P20") (pinfunction "GNDISO_P20") (pintype "bidirectional"))
      (node (ref "U8") (pin "2") (pinfunction "C1_2") (pintype "passive"))
      (node (ref "U8") (pin "3") (pinfunction "C2_3") (pintype "passive"))
    )
    (net (code "17") (name "INT_RTC") (class "Default")
      (node (ref "U1") (pin "38") (pinfunction "GPIO26/ADC0_38") (pintype "bidirectional"))
      (node (ref "U10") (pin "3") (pinfunction "~{INT}_3") (pintype "output"))
    )
    (net (code "18") (name "INT_SOIL") (class "Default")
      (node (ref "R14") (pin "1") (pinfunction "1_1") (pintype "passive"))
      (node (ref "U1") (pin "3") (pinfunction "GPIO1_3") (pintype "bidirectional"))
      (node (ref "U8") (pin "7") (pinfunction "C1(VO1)_7") (pintype "passive"))
    )
    (net (code "19") (name "INT_SOILTEMP") (class "Default")
      (node (ref "R15") (pin "1") (pinfunction "1_1") (pintype "passive"))
      (node (ref "U1") (pin "4") (pinfunction "GPIO2_4") (pintype "bidirectional"))
      (node (ref "U8") (pin "6") (pinfunction "C2(VO2)_6") (pintype "passive"))
    )
    (net (code "20") (name "INT_SOILTEMP_ISO") (class "Default")
      (node (ref "R16") (pin "1") (pinfunction "1_1") (pintype "passive"))
      (node (ref "U$3") (pin "P$7") (pinfunction "INT_P$7") (pintype "bidirectional"))
    )
    (net (code "21") (name "INT_SOIL_ISO") (class "Default")
      (node (ref "R17") (pin "1") (pinfunction "1_1") (pintype "passive"))
      (node (ref "U$2") (pin "P$7") (pinfunction "INT_P$7") (pintype "bidirectional"))
    )
    (net (code "22") (name "IRQ_LIGHTNING") (class "Default")
      (node (ref "U1") (pin "9") (pinfunction "GPIO7_9") (pintype "bidirectional"))
      (node (ref "U9") (pin "10") (pinfunction "IRQ_10") (pintype "output"))
    )
    (net (code "23") (name "NEOPIXEL_3.3V") (class "Default")
      (node (ref "U1") (pin "27") (pinfunction "GPIO16_27") (pintype "bidirectional"))
      (node (ref "U15") (pin "3") (pinfunction "A_3") (pintype "input"))
    )
    (net (code "24") (name "NEOPIXEL_5V") (class "Default")
      (node (ref "U11") (pin "P$4") (pinfunction "DI_P$4") (pintype "bidirectional"))
      (node (ref "U15") (pin "4") (pinfunction "B_4") (pintype "output"))
    )
    (net (code "25") (name "Net-(C21-Pad1)") (class "Default")
      (node (ref "C21") (pin "1") (pinfunction "1_1") (pintype "passive"))
      (node (ref "J2") (pin "A4_B9") (pinfunction "VBUS_A4_B9") (pintype "power_in"))
      (node (ref "J2") (pin "B4_A9") (pinfunction "VBUS_B4_A9") (pintype "power_in"))
      (node (ref "L2") (pin "1") (pinfunction "1_1") (pintype "passive"))
    )
    (net (code "26") (name "Net-(C43-+)") (class "Default")
      (node (ref "C43") (pin "1") (pinfunction "+_1") (pintype "bidirectional"))
      (node (ref "C46") (pin "1") (pinfunction "1_1") (pintype "passive"))
      (node (ref "D2") (pin "C") (pinfunction "C_C") (pintype "passive"))
      (node (ref "U10") (pin "8") (pinfunction "VDD_8") (pintype "power_in"))
    )
    (net (code "27") (name "Net-(D3-PadA)") (class "Default")
      (node (ref "D3") (pin "A") (pinfunction "A_A") (pintype "passive"))
      (node (ref "R4") (pin "2") (pinfunction "2_2") (pintype "passive"))
    )
    (net (code "28") (name "Net-(J2-CC1)") (class "Default")
      (node (ref "J2") (pin "A5") (pinfunction "CC1_A5") (pintype "bidirectional"))
      (node (ref "R10") (pin "2") (pinfunction "2_2") (pintype "passive"))
    )
    (net (code "29") (name "Net-(J2-CC2)") (class "Default")
      (node (ref "J2") (pin "B5") (pinfunction "CC2_B5") (pintype "bidirectional"))
      (node (ref "R9") (pin "2") (pinfunction "2_2") (pintype "passive"))
    )
    (net (code "30") (name "Net-(Q2-D)") (class "Default")
      (node (ref "D1") (pin "A") (pinfunction "A_A") (pintype "passive"))
      (node (ref "LS1") (pin "N") (pinfunction "N_N") (pintype "passive"))
      (node (ref "Q2") (pin "3") (pinfunction "D_3") (pintype "passive"))
    )
    (net (code "31") (name "Net-(Q2-G)") (class "Default")
      (node (ref "Q2") (pin "1") (pinfunction "G_1") (pintype "passive"))
      (node (ref "R25") (pin "1") (pinfunction "1_1") (pintype "passive"))
    )
    (net (code "32") (name "Net-(Q3-X2)") (class "Default")
      (node (ref "C12") (pin "2") (pinfunction "2_2") (pintype "passive"))
      (node (ref "Q3") (pin "3") (pinfunction "X2_3") (pintype "bidirectional"))
      (node (ref "R7") (pin "1") (pinfunction "1_1") (pintype "passive"))
    )
    (net (code "33") (name "Net-(R2-Pad1)") (class "Default")
      (node (ref "R2") (pin "1") (pinfunction "1_1") (pintype "passive"))
      (node (ref "RESET") (pin "3") (pinfunction "2_3") (pintype "passive"))
      (node (ref "RESET") (pin "4") (pinfunction "2_4") (pintype "passive"))
    )
    (net (code "34") (name "Net-(U3-IO8)") (class "Default")
      (node (ref "R13") (pin "1") (pinfunction "1_1") (pintype "passive"))
      (node (ref "U3") (pin "22") (pinfunction "IO8_22") (pintype "bidirectional"))
    )
    (net (code "35") (name "Net-(U6-VSEL)") (class "Default")
      (node (ref "R19") (pin "1") (pinfunction "1_1") (pintype "passive"))
      (node (ref "R20") (pin "2") (pinfunction "2_2") (pintype "passive"))
      (node (ref "U6") (pin "P13") (pinfunction "VSEL_P13") (pintype "bidirectional"))
    )
    (net (code "36") (name "Net-(U8-A1)") (class "Default")
      (node (ref "R17") (pin "2") (pinfunction "2_2") (pintype "passive"))
      (node (ref "U8") (pin "1") (pinfunction "A1_1") (pintype "passive"))
    )
    (net (code "37") (name "Net-(U8-A2)") (class "Default")
      (node (ref "R16") (pin "2") (pinfunction "2_2") (pintype "passive"))
      (node (ref "U8") (pin "4") (pinfunction "A2_4") (pintype "passive"))
    )
    (net (code "38") (name "Net-(U9-ACG)") (class "Default")
      (node (ref "C31") (pin "1") (pinfunction "1_1") (pintype "passive"))
      (node (ref "U9") (pin "1") (pinfunction "ACG_1") (pintype "passive"))
    )
    (net (code "39") (name "Net-(U9-INP)") (class "Default")
      (node (ref "C33") (pin "1") (pinfunction "1_1") (pintype "passive"))
      (node (ref "L3") (pin "2") (pinfunction "2_2") (pintype "passive"))
      (node (ref "R18") (pin "2") (pinfunction "2_2") (pintype "passive"))
      (node (ref "U9") (pin "3") (pinfunction "INP_3") (pintype "bidirectional"))
    )
    (net (code "40") (name "Net-(U10-OSCI)") (class "Default")
      (node (ref "C47") (pin "2") (pinfunction "2_2") (pintype "passive"))
      (node (ref "U10") (pin "1") (pinfunction "OSCI_1") (pintype "input"))
      (node (ref "XTAL1") (pin "2") (pinfunction "2_2") (pintype "passive"))
    )
    (net (code "41") (name "Net-(U10-OSCO)") (class "Default")
      (node (ref "C48") (pin "2") (pinfunction "2_2") (pintype "passive"))
      (node (ref "U10") (pin "2") (pinfunction "OSCO_2") (pintype "output"))
      (node (ref "XTAL1") (pin "1") (pinfunction "1_1") (pintype "passive"))
    )
    (net (code "42") (name "Net-(U11-DO)") (class "Default")
      (node (ref "U11") (pin "P$2") (pinfunction "DO_P$2") (pintype "bidirectional"))
      (node (ref "U12") (pin "P$4") (pinfunction "DI_P$4") (pintype "bidirectional"))
    )
    (net (code "43") (name "Net-(U12-DO)") (class "Default")
      (node (ref "U12") (pin "P$2") (pinfunction "DO_P$2") (pintype "bidirectional"))
      (node (ref "U13") (pin "P$4") (pinfunction "DI_P$4") (pintype "bidirectional"))
    )
    (net (code "44") (name "Net-(U13-DO)") (class "Default")
      (node (ref "U13") (pin "P$2") (pinfunction "DO_P$2") (pintype "bidirectional"))
      (node (ref "U14") (pin "P$4") (pinfunction "DI_P$4") (pintype "bidirectional"))
    )
    (net (code "45") (name "PDIS") (class "Default")
      (node (ref "Q1") (pin "3") (pinfunction "D_3") (pintype "passive"))
      (node (ref "R23") (pin "1") (pinfunction "1_1") (pintype "passive"))
      (node (ref "U6") (pin "P8") (pinfunction "PDIS_P8") (pintype "bidirectional"))
    )
    (net (code "46") (name "PDIS_EN") (class "Default")
      (node (ref "Q1") (pin "1") (pinfunction "G_1") (pintype "passive"))
      (node (ref "R24") (pin "1") (pinfunction "1_1") (pintype "passive"))
      (node (ref "U1") (pin "11") (pinfunction "GPIO8_11") (pintype "bidirectional"))
    )
    (net (code "47") (name "PRB1") (class "Default")
      (node (ref "J4") (pin "1") (pinfunction "1_1") (pintype "passive"))
      (node (ref "U$2") (pin "P$4") (pinfunction "PRB_P$4") (pintype "bidirectional"))
    )
    (net (code "48") (name "PRB1_GND") (class "Default")
      (node (ref "J4") (pin "2") (pinfunction "2_2") (pintype "passive"))
      (node (ref "J4") (pin "3") (pinfunction "2_3") (pintype "passive"))
      (node (ref "U$2") (pin "P$5") (pinfunction "PRB_GND_P$5") (pintype "bidirectional"))
    )
    (net (code "49") (name "PROBE2") (class "Default")
      (node (ref "J5") (pin "1") (pinfunction "1_1") (pintype "passive"))
      (node (ref "U$3") (pin "P$4") (pinfunction "PRB_P$4") (pintype "bidirectional"))
    )
    (net (code "50") (name "PROBE2_GND") (class "Default")
      (node (ref "J5") (pin "2") (pinfunction "2_2") (pintype "passive"))
      (node (ref "J5") (pin "3") (pinfunction "2_3") (pintype "passive"))
      (node (ref "U$3") (pin "P$5") (pinfunction "PRB_GND_P$5") (pintype "bidirectional"))
    )
    (net (code "51") (name "QSPI_SCLK") (class "Default")
      (node (ref "IC1") (pin "6") (pinfunction "CLK_6") (pintype "bidirectional"))
      (node (ref "U1") (pin "52") (pinfunction "QSPI_SCLK_52") (pintype "bidirectional"))
    )
    (net (code "52") (name "QSPI_SD0") (class "Default")
      (node (ref "IC1") (pin "5") (pinfunction "DI(IO0)_5") (pintype "bidirectional"))
      (node (ref "U1") (pin "53") (pinfunction "QSPI_SD0_53") (pintype "bidirectional"))
    )
    (net (code "53") (name "QSPI_SD1") (class "Default")
      (node (ref "IC1") (pin "2") (pinfunction "DO(IO1)_2") (pintype "bidirectional"))
      (node (ref "U1") (pin "55") (pinfunction "QSPI_SD1_55") (pintype "bidirectional"))
    )
    (net (code "54") (name "QSPI_SD2") (class "Default")
      (node (ref "IC1") (pin "3") (pinfunction "~{WP(IO2})_3") (pintype "bidirectional"))
      (node (ref "U1") (pin "54") (pinfunction "QSPI_SD2_54") (pintype "bidirectional"))
    )
    (net (code "55") (name "QSPI_SD3") (class "Default")
      (node (ref "IC1") (pin "7") (pinfunction "~{HOLD_OR_}RESET_(IO3)_7") (pintype "bidirectional"))
      (node (ref "U1") (pin "51") (pinfunction "QSPI_SD3_51") (pintype "bidirectional"))
    )
    (net (code "56") (name "SCL") (class "Default")
      (node (ref "J3") (pin "4") (pinfunction "4_4") (pintype "passive"))
      (node (ref "R12") (pin "1") (pinfunction "1_1") (pintype "passive"))
      (node (ref "U1") (pin "37") (pinfunction "GPIO25_37") (pintype "bidirectional"))
      (node (ref "U10") (pin "6") (pinfunction "SCL_6") (pintype "input"))
      (node (ref "U5") (pin "4") (pinfunction "SCK_4") (pintype "input"))
      (node (ref "U6") (pin "P2") (pinfunction "SCL2_P2") (pintype "bidirectional"))
      (node (ref "U7") (pin "2") (pinfunction "SCL_2") (pintype "input"))
      (node (ref "U9") (pin "11") (pinfunction "I2CL/SCL_11") (pintype "input"))
    )
    (net (code "57") (name "SCL_ISO") (class "Default")
      (node (ref "R22") (pin "1") (pinfunction "1_1") (pintype "passive"))
      (node (ref "U$2") (pin "P$8") (pinfunction "SCL_P$8") (pintype "bidirectional"))
      (node (ref "U$3") (pin "P$8") (pinfunction "SCL_P$8") (pintype "bidirectional"))
      (node (ref "U6") (pin "P19") (pinfunction "SCL1_P19") (pintype "bidirectional"))
    )
    (net (code "58") (name "SDA") (class "Default")
      (node (ref "J3") (pin "3") (pinfunction "3_3") (pintype "passive"))
      (node (ref "R11") (pin "1") (pinfunction "1_1") (pintype "passive"))
      (node (ref "U1") (pin "36") (pinfunction "GPIO24_36") (pintype "bidirectional"))
      (node (ref "U10") (pin "5") (pinfunction "SDA_5") (pintype "bidirectional"))
      (node (ref "U5") (pin "3") (pinfunction "SDI_3") (pintype "bidirectional"))
      (node (ref "U6") (pin "P3") (pinfunction "SDA2_P3") (pintype "bidirectional"))
      (node (ref "U7") (pin "3") (pinfunction "SDA_3") (pintype "bidirectional"))
      (node (ref "U9") (pin "13") (pinfunction "I2CD/MOSI_13") (pintype "bidirectional"))
    )
    (net (code "59") (name "SDA_ISO") (class "Default")
      (node (ref "R21") (pin "1") (pinfunction "1_1") (pintype "passive"))
      (node (ref "U$2") (pin "P$1") (pinfunction "SDA_P$1") (pintype "bidirectional"))
      (node (ref "U$3") (pin "P$1") (pinfunction "SDA_P$1") (pintype "bidirectional"))
      (node (ref "U6") (pin "P18") (pinfunction "SDA1_P18") (pintype "bidirectional"))
    )
    (net (code "60") (name "SD_CLK") (class "Default")
      (node (ref "U$1") (pin "P5") (pinfunction "CLK_P5") (pintype "bidirectional"))
      (node (ref "U1") (pin "17") (pinfunction "GPIO14_17") (pintype "bidirectional"))
    )
    (net (code "61") (name "SWCLK") (class "Default")
      (node (ref "J1") (pin "1") (pinfunction "1_1") (pintype "passive"))
      (node (ref "U1") (pin "24") (pinfunction "SWCLK_24") (pintype "input"))
    )
    (net (code "62") (name "SWD") (class "Default")
      (node (ref "J1") (pin "3") (pinfunction "3_3") (pintype "passive"))
      (node (ref "U1") (pin "25") (pinfunction "SWD_25") (pintype "bidirectional"))
    )
    (net (code "63") (name "SWITCH") (class "Default")
      (node (ref "U$1") (pin "G1") (pinfunction "SWITCH_G1") (pintype "bidirectional"))
      (node (ref "U1") (pin "12") (pinfunction "GPIO9_12") (pintype "bidirectional"))
    )
    (net (code "64") (name "USBIN_N") (class "Default")
      (node (ref "R1") (pin "1") (pinfunction "1_1") (pintype "passive"))
      (node (ref "U1") (pin "46") (pinfunction "USB_DM_46") (pintype "bidirectional"))
    )
    (net (code "65") (name "USBIN_P") (class "Default")
      (node (ref "R3") (pin "1") (pinfunction "1_1") (pintype "passive"))
      (node (ref "U1") (pin "47") (pinfunction "USB_DP_47") (pintype "bidirectional"))
    )
    (net (code "66") (name "USB_N") (class "Default")
      (node (ref "J2") (pin "A7") (pinfunction "DN1_A7") (pintype "bidirectional"))
      (node (ref "J2") (pin "B7") (pinfunction "DN2_B7") (pintype "bidirectional"))
      (node (ref "R1") (pin "2") (pinfunction "2_2") (pintype "passive"))
    )
    (net (code "67") (name "USB_P") (class "Default")
      (node (ref "J2") (pin "A6") (pinfunction "DP1_A6") (pintype "bidirectional"))
      (node (ref "J2") (pin "B6") (pinfunction "DP2_B6") (pintype "bidirectional"))
      (node (ref "R3") (pin "2") (pinfunction "2_2") (pintype "passive"))
    )
    (net (code "68") (name "USR_BUTTON") (class "Default")
      (node (ref "U1") (pin "5") (pinfunction "GPIO3_5") (pintype "bidirectional"))
      (node (ref "USER_BUTTON") (pin "1") (pinfunction "1_1") (pintype "passive"))
      (node (ref "USER_BUTTON") (pin "2") (pinfunction "1_2") (pintype "passive"))
    )
    (net (code "69") (name "USR_LED") (class "Default")
      (node (ref "R4") (pin "1") (pinfunction "1_1") (pintype "passive"))
      (node (ref "U1") (pin "2") (pinfunction "GPIO0_2") (pintype "bidirectional"))
    )
    (net (code "70") (name "VCC-ISO") (class "Default")
      (node (ref "C37") (pin "1") (pinfunction "1_1") (pintype "passive"))
      (node (ref "C38") (pin "1") (pinfunction "1_1") (pintype "passive"))
      (node (ref "C39") (pin "1") (pinfunction "1_1") (pintype "passive"))
      (node (ref "C40") (pin "2") (pinfunction "2_2") (pintype "passive"))
      (node (ref "C41") (pin "2") (pinfunction "2_2") (pintype "passive"))
      (node (ref "R19") (pin "2") (pinfunction "2_2") (pintype "passive"))
      (node (ref "R21") (pin "2") (pinfunction "2_2") (pintype "passive"))
      (node (ref "R22") (pin "2") (pinfunction "2_2") (pintype "passive"))
      (node (ref "U$2") (pin "P$3") (pinfunction "VCC_P$3") (pintype "power_in"))
      (node (ref "U$3") (pin "P$3") (pinfunction "VCC_P$3") (pintype "power_in"))
      (node (ref "U6") (pin "P12") (pinfunction "VISO_P12") (pintype "bidirectional"))
      (node (ref "U6") (pin "P17") (pinfunction "VDDISO_P17") (pintype "bidirectional"))
    )
    (net (code "71") (name "VOUT") (class "Default")
      (node (ref "C1") (pin "1") (pinfunction "1_1") (pintype "passive"))
      (node (ref "C2") (pin "1") (pinfunction "1_1") (pintype "passive"))
      (node (ref "C3") (pin "1") (pinfunction "1_1") (pintype "passive"))
      (node (ref "U1") (pin "23") (pinfunction "DVDD_23") (pintype "power_in"))
      (node (ref "U1") (pin "45") (pinfunction "VREG_VOUT_45") (pintype "output"))
      (node (ref "U1") (pin "50") (pinfunction "DVDD_50") (pintype "power_in"))
    )
    (net (code "72") (name "V_USB") (class "Default")
      (node (ref "C22") (pin "1") (pinfunction "1_1") (pintype "passive"))
      (node (ref "C23") (pin "2") (pinfunction "2_2") (pintype "passive"))
      (node (ref "C34") (pin "2") (pinfunction "2_2") (pintype "passive"))
      (node (ref "C35") (pin "2") (pinfunction "2_2") (pintype "passive"))
      (node (ref "C45") (pin "1") (pinfunction "1_1") (pintype "passive"))
      (node (ref "C49") (pin "1") (pinfunction "1_1") (pintype "passive"))
      (node (ref "C50") (pin "1") (pinfunction "1_1") (pintype "passive"))
      (node (ref "C51") (pin "1") (pinfunction "1_1") (pintype "passive"))
      (node (ref "C52") (pin "1") (pinfunction "1_1") (pintype "passive"))
      (node (ref "L2") (pin "2") (pinfunction "2_2") (pintype "passive"))
      (node (ref "R23") (pin "2") (pinfunction "2_2") (pintype "passive"))
      (node (ref "U11") (pin "P$1") (pinfunction "VCC_P$1") (pintype "bidirectional"))
      (node (ref "U12") (pin "P$1") (pinfunction "VCC_P$1") (pintype "bidirectional"))
      (node (ref "U13") (pin "P$1") (pinfunction "VCC_P$1") (pintype "bidirectional"))
      (node (ref "U14") (pin "P$1") (pinfunction "VCC_P$1") (pintype "bidirectional"))
      (node (ref "U15") (pin "6") (pinfunction "VCCB_6") (pintype "power_in"))
      (node (ref "U4") (pin "1") (pinfunction "VIN_1") (pintype "input"))
      (node (ref "U4") (pin "3") (pinfunction "EN_3") (pintype "input"))
      (node (ref "U6") (pin "P9") (pinfunction "VIN_P9") (pintype "bidirectional"))
      (node (ref "USB") (pin "TP") (pinfunction "TP_TP") (pintype "input"))
    )
    (net (code "73") (name "XIN") (class "Default")
      (node (ref "C13") (pin "2") (pinfunction "2_2") (pintype "passive"))
      (node (ref "Q3") (pin "1") (pinfunction "X1_1") (pintype "bidirectional"))
      (node (ref "U1") (pin "20") (pinfunction "XIN_20") (pintype "input"))
    )
    (net (code "74") (name "XOUT") (class "Default")
      (node (ref "R7") (pin "2") (pinfunction "2_2") (pintype "passive"))
      (node (ref "U1") (pin "21") (pinfunction "XOUT_21") (pintype "output"))
    )
    (net (code "75") (name "unconnected-(J2-SBU1-PadA8)") (class "Default")
      (node (ref "J2") (pin "A8") (pinfunction "SBU1_A8") (pintype "bidirectional"))
    )
    (net (code "76") (name "unconnected-(J2-SBU2-PadB8)") (class "Default")
      (node (ref "J2") (pin "B8") (pinfunction "SBU2_B8") (pintype "bidirectional"))
    )
    (net (code "77") (name "unconnected-(J6-Pad01)") (class "Default")
      (node (ref "J6") (pin "01") (pinfunction "01_01") (pintype "passive"))
    )
    (net (code "78") (name "unconnected-(J6-Pad02)") (class "Default")
      (node (ref "J6") (pin "02") (pinfunction "02_02") (pintype "passive"))
    )
    (net (code "79") (name "unconnected-(U$2-NC-PadP$2)") (class "Default")
      (node (ref "U$2") (pin "P$2") (pinfunction "NC_P$2") (pintype "no_connect"))
    )
    (net (code "80") (name "unconnected-(U$2-NC-PadP$9)") (class "Default")
      (node (ref "U$2") (pin "P$9") (pinfunction "NC_P$9") (pintype "no_connect"))
    )
    (net (code "81") (name "unconnected-(U$2-NC-PadP$10)") (class "Default")
      (node (ref "U$2") (pin "P$10") (pinfunction "NC_P$10") (pintype "no_connect"))
    )
    (net (code "82") (name "unconnected-(U$3-NC-PadP$2)") (class "Default")
      (node (ref "U$3") (pin "P$2") (pinfunction "NC_P$2") (pintype "no_connect"))
    )
    (net (code "83") (name "unconnected-(U$3-NC-PadP$9)") (class "Default")
      (node (ref "U$3") (pin "P$9") (pinfunction "NC_P$9") (pintype "no_connect"))
    )
    (net (code "84") (name "unconnected-(U$3-NC-PadP$10)") (class "Default")
      (node (ref "U$3") (pin "P$10") (pinfunction "NC_P$10") (pintype "no_connect"))
    )
    (net (code "85") (name "unconnected-(U1-GPIO27{slash}ADC1-Pad39)") (class "Default")
      (node (ref "U1") (pin "39") (pinfunction "GPIO27/ADC1_39") (pintype "bidirectional"))
    )
    (net (code "86") (name "unconnected-(U1-GPIO28{slash}ADC2-Pad40)") (class "Default")
      (node (ref "U1") (pin "40") (pinfunction "GPIO28/ADC2_40") (pintype "bidirectional"))
    )
    (net (code "87") (name "unconnected-(U1-GPIO29{slash}ADC3-Pad41)") (class "Default")
      (node (ref "U1") (pin "41") (pinfunction "GPIO29/ADC3_41") (pintype "bidirectional"))
    )
    (net (code "88") (name "unconnected-(U3-IO0-Pad12)") (class "Default")
      (node (ref "U3") (pin "12") (pinfunction "IO0_12") (pintype "bidirectional"))
    )
    (net (code "89") (name "unconnected-(U3-IO1-Pad13)") (class "Default")
      (node (ref "U3") (pin "13") (pinfunction "IO1_13") (pintype "bidirectional"))
    )
    (net (code "90") (name "unconnected-(U3-IO4-Pad18)") (class "Default")
      (node (ref "U3") (pin "18") (pinfunction "IO4_18") (pintype "bidirectional"))
    )
    (net (code "91") (name "unconnected-(U3-IO5-Pad19)") (class "Default")
      (node (ref "U3") (pin "19") (pinfunction "IO5_19") (pintype "bidirectional"))
    )
    (net (code "92") (name "unconnected-(U3-IO18-Pad26)") (class "Default")
      (node (ref "U3") (pin "26") (pinfunction "IO18_26") (pintype "bidirectional"))
    )
    (net (code "93") (name "unconnected-(U3-IO19-Pad27)") (class "Default")
      (node (ref "U3") (pin "27") (pinfunction "IO19_27") (pintype "bidirectional"))
    )
    (net (code "94") (name "unconnected-(U3-NC-Pad4)") (class "Default")
      (node (ref "U3") (pin "4") (pinfunction "NC_4") (pintype "no_connect"))
    )
    (net (code "95") (name "unconnected-(U3-NC-Pad7)") (class "Default")
      (node (ref "U3") (pin "7") (pinfunction "NC_7") (pintype "no_connect"))
    )
    (net (code "96") (name "unconnected-(U3-NC-Pad9)") (class "Default")
      (node (ref "U3") (pin "9") (pinfunction "NC_9") (pintype "no_connect"))
    )
    (net (code "97") (name "unconnected-(U3-NC-Pad10)") (class "Default")
      (node (ref "U3") (pin "10") (pinfunction "NC_10") (pintype "no_connect"))
    )
    (net (code "98") (name "unconnected-(U3-NC-Pad15)") (class "Default")
      (node (ref "U3") (pin "15") (pinfunction "NC_15") (pintype "no_connect"))
    )
    (net (code "99") (name "unconnected-(U3-NC-Pad17)") (class "Default")
      (node (ref "U3") (pin "17") (pinfunction "NC_17") (pintype "no_connect"))
    )
    (net (code "100") (name "unconnected-(U3-NC-Pad24)") (class "Default")
      (node (ref "U3") (pin "24") (pinfunction "NC_24") (pintype "no_connect"))
    )
    (net (code "101") (name "unconnected-(U3-NC-Pad25)") (class "Default")
      (node (ref "U3") (pin "25") (pinfunction "NC_25") (pintype "no_connect"))
    )
    (net (code "102") (name "unconnected-(U3-NC-Pad28)") (class "Default")
      (node (ref "U3") (pin "28") (pinfunction "NC_28") (pintype "no_connect"))
    )
    (net (code "103") (name "unconnected-(U3-NC-Pad29)") (class "Default")
      (node (ref "U3") (pin "29") (pinfunction "NC_29") (pintype "no_connect"))
    )
    (net (code "104") (name "unconnected-(U3-NC-Pad32)") (class "Default")
      (node (ref "U3") (pin "32") (pinfunction "NC_32") (pintype "no_connect"))
    )
    (net (code "105") (name "unconnected-(U3-NC-Pad33)") (class "Default")
      (node (ref "U3") (pin "33") (pinfunction "NC_33") (pintype "no_connect"))
    )
    (net (code "106") (name "unconnected-(U3-NC-Pad34)") (class "Default")
      (node (ref "U3") (pin "34") (pinfunction "NC_34") (pintype "no_connect"))
    )
    (net (code "107") (name "unconnected-(U3-NC-Pad35)") (class "Default")
      (node (ref "U3") (pin "35") (pinfunction "NC_35") (pintype "no_connect"))
    )
    (net (code "108") (name "unconnected-(U9-NC-Pad14)") (class "Default")
      (node (ref "U9") (pin "14") (pinfunction "NC_14") (pintype "no_connect"))
    )
    (net (code "109") (name "unconnected-(U10-CLKOUT-Pad7)") (class "Default")
      (node (ref "U10") (pin "7") (pinfunction "CLKOUT_7") (pintype "output"))
    )
    (net (code "110") (name "unconnected-(U14-DO-PadP$2)") (class "Default")
      (node (ref "U14") (pin "P$2") (pinfunction "DO_P$2") (pintype "bidirectional"))
    )
    (net (code "111") (name "~{ESP32_BOOT}") (class "Default")
      (node (ref "U1") (pin "30") (pinfunction "GPIO19_30") (pintype "bidirectional"))
      (node (ref "U3") (pin "23") (pinfunction "IO9_23") (pintype "bidirectional"))
    )
    (net (code "112") (name "~{ESP32_RST}") (class "Default")
      (node (ref "U1") (pin "29") (pinfunction "GPIO18_29") (pintype "bidirectional"))
      (node (ref "U3") (pin "8") (pinfunction "EN_8") (pintype "input"))
    )
    (net (code "113") (name "~{QSPI_CS}") (class "Default")
      (node (ref "IC1") (pin "1") (pinfunction "~{CS}_1") (pintype "bidirectional"))
      (node (ref "R5") (pin "1") (pinfunction "1_1") (pintype "passive"))
      (node (ref "R6") (pin "2") (pinfunction "2_2") (pintype "passive"))
      (node (ref "U1") (pin "56") (pinfunction "QSPI_CSN_56") (pintype "bidirectional"))
    )
    (net (code "114") (name "~{RESET}") (class "Default")
      (node (ref "RESET") (pin "1") (pinfunction "1_1") (pintype "passive"))
      (node (ref "RESET") (pin "2") (pinfunction "1_2") (pintype "passive"))
      (node (ref "U1") (pin "26") (pinfunction "RUN_26") (pintype "input"))
    )
    (net (code "115") (name "~{USB_BOOT}") (class "Default")
      (node (ref "!BOOT") (pin "3") (pinfunction "2_3") (pintype "passive"))
      (node (ref "!BOOT") (pin "4") (pinfunction "2_4") (pintype "passive"))
      (node (ref "R6") (pin "1") (pinfunction "1_1") (pintype "passive"))
    )
  )
)
